# levitator_v1_2023_05_06_11_59_24_UTC.net
KiCad netlist of a schematic drawn in EAGLE
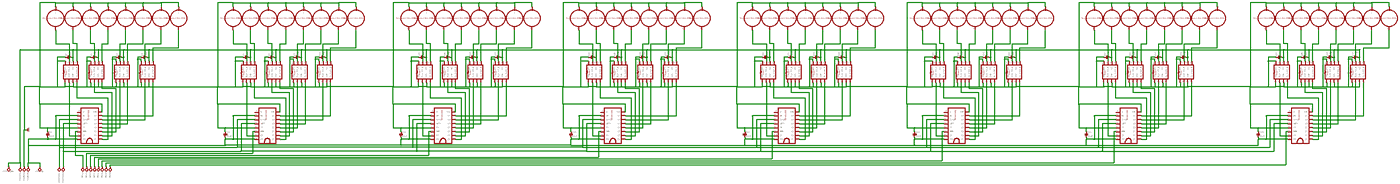
[diagram p0: schematic, sheet 1, overview]
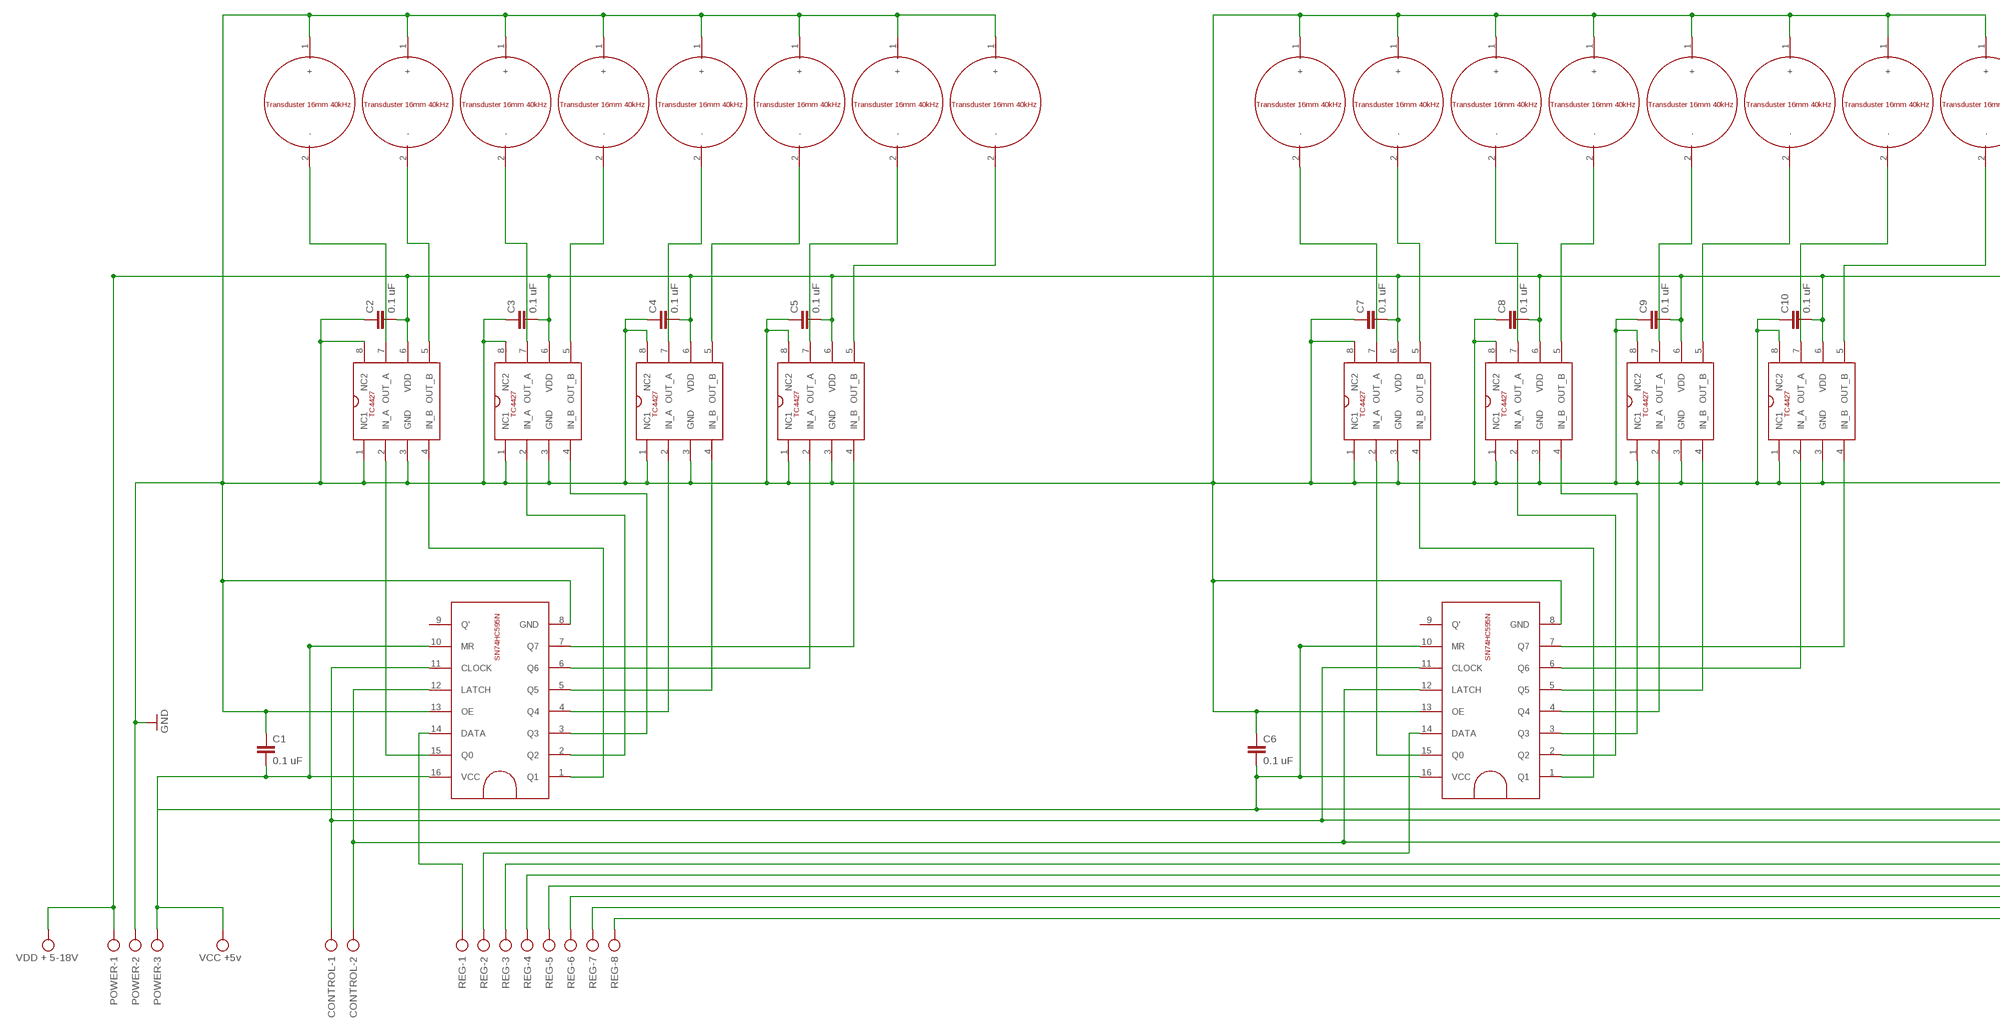
[diagram p1: schematic, sheet 1, part 1 of 4]
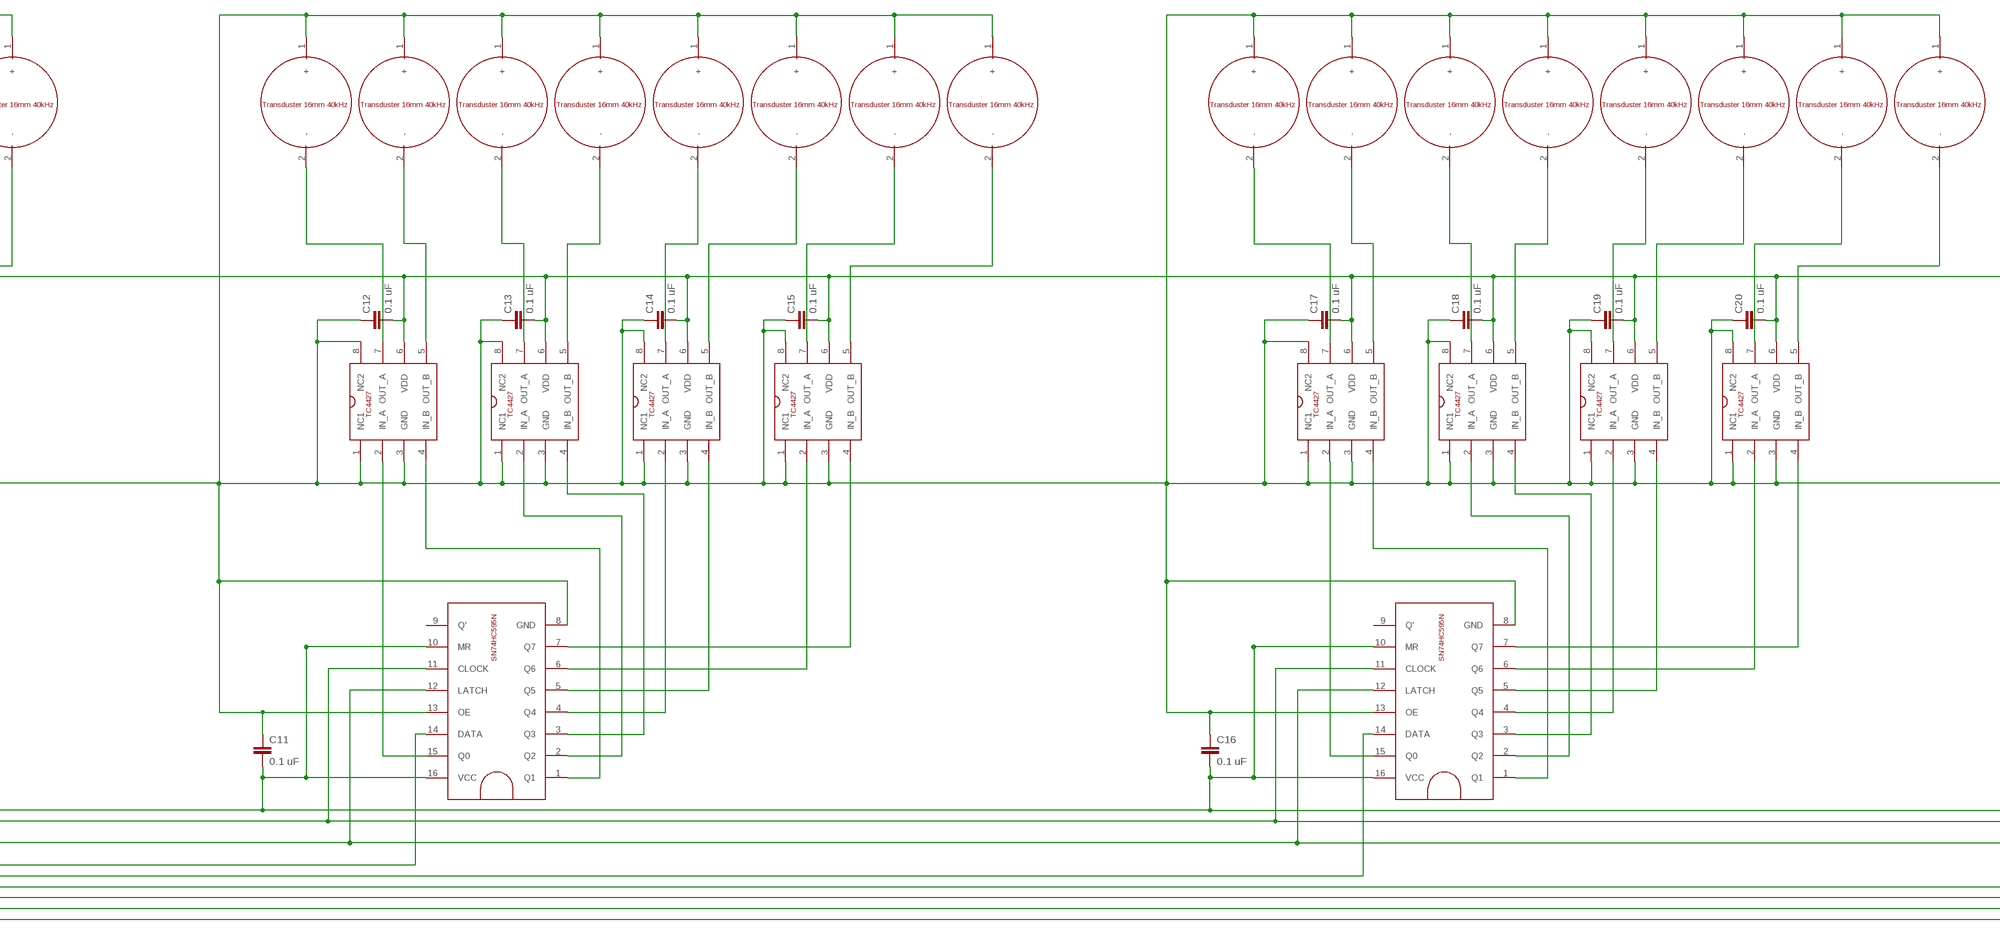
[diagram p2: schematic, sheet 1, part 2 of 4]
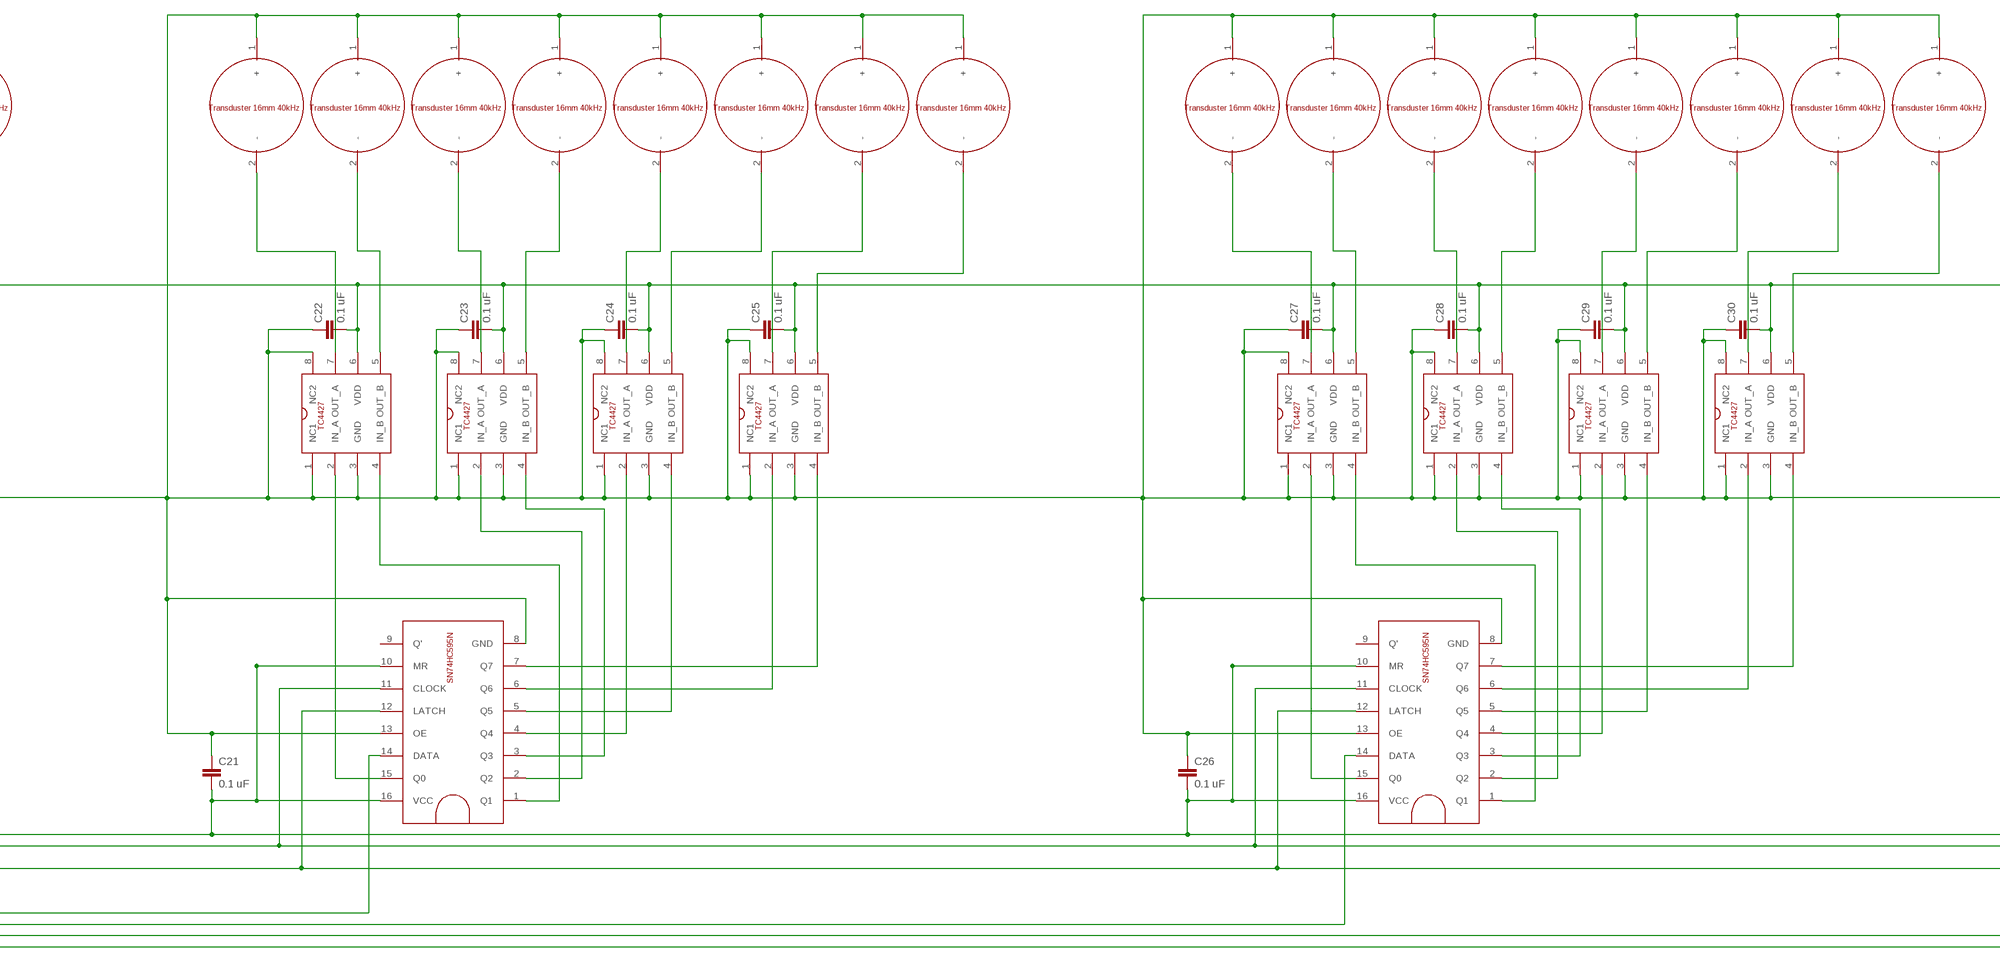
[diagram p3: schematic, sheet 1, part 3 of 4]
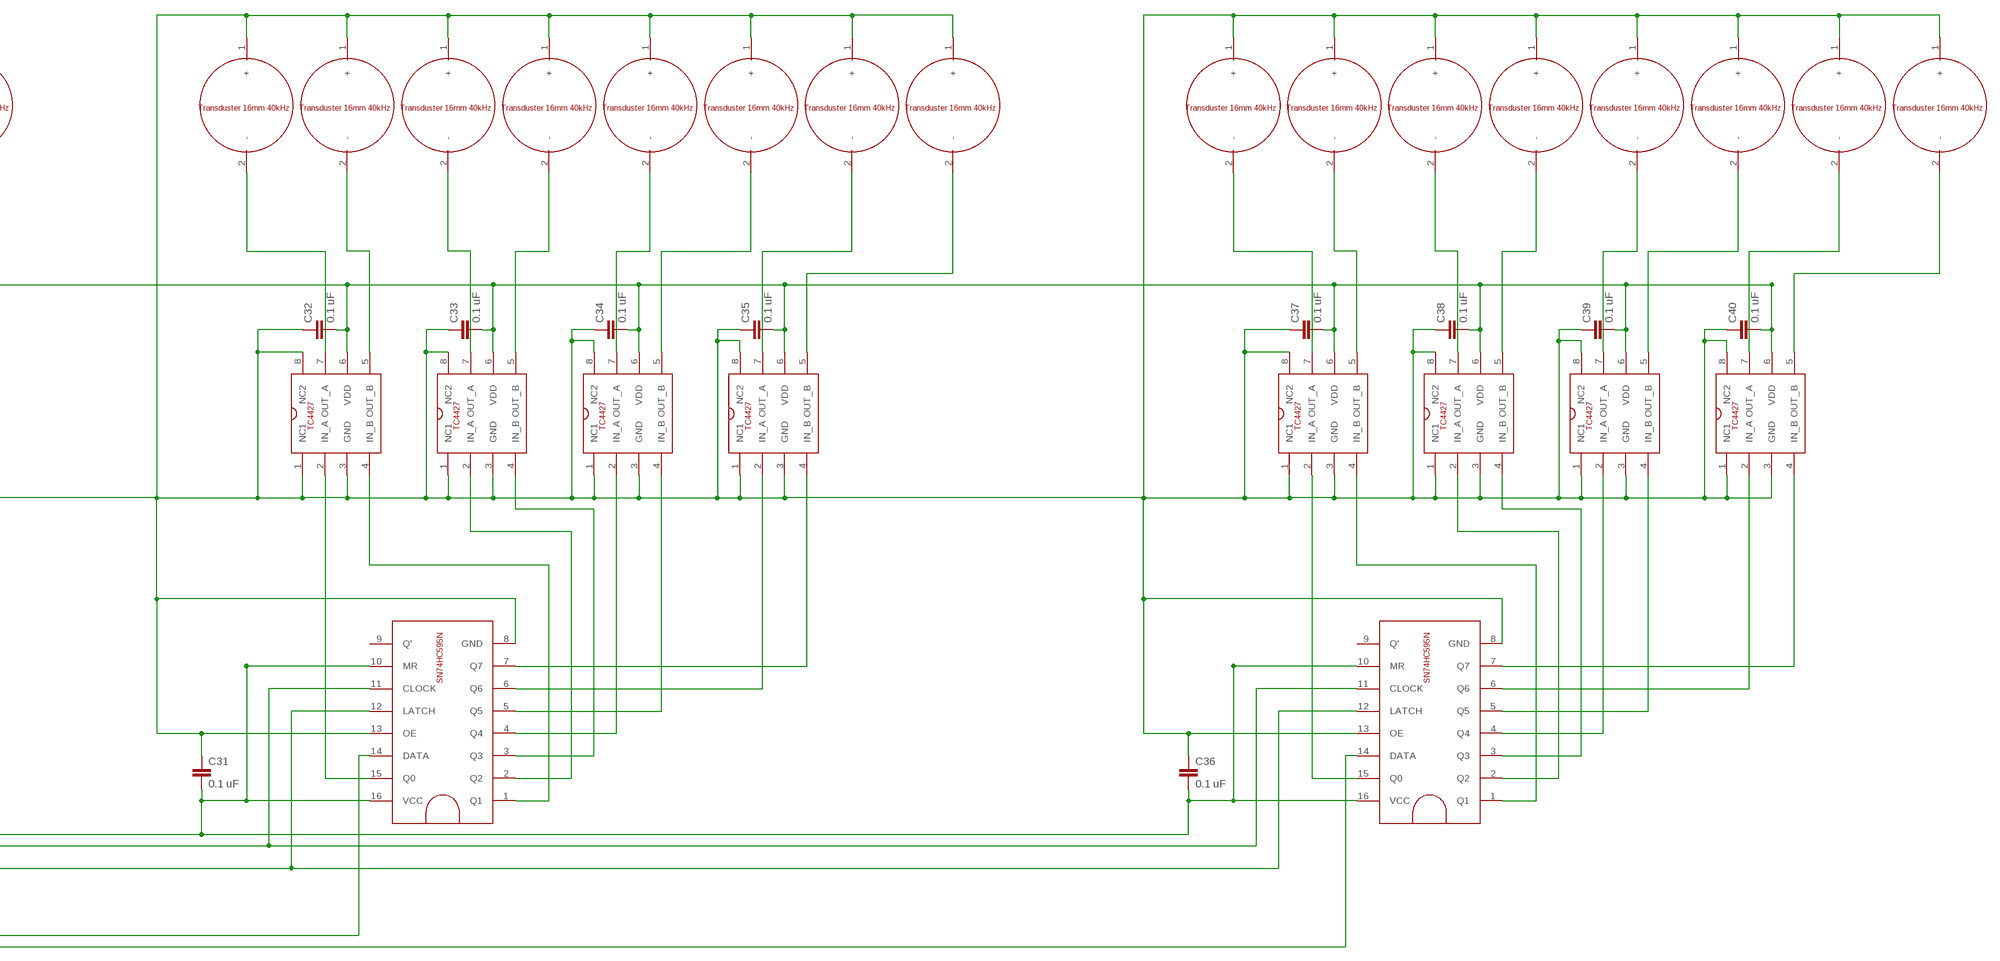
[diagram p4: schematic, sheet 1, part 4 of 4]

(export (version "E")
  (design (tool "Eeschema 10.0.6"))
  (components
    (comp (ref "C1")
      (value "0.1 uF")
      (footprint "eagle-import:C025-025X050")
      (libsource (lib "eagle-import") (part "C-EU025-025X050"))
    )
    (comp (ref "C2")
      (value "0.1 uF")
      (footprint "eagle-import:C025-025X050")
      (libsource (lib "eagle-import") (part "C-EU025-025X050"))
    )
    (comp (ref "C3")
      (value "0.1 uF")
      (footprint "eagle-import:C025-025X050")
      (libsource (lib "eagle-import") (part "C-EU025-025X050"))
    )
    (comp (ref "C4")
      (value "0.1 uF")
      (footprint "eagle-import:C025-025X050")
      (libsource (lib "eagle-import") (part "C-EU025-025X050"))
    )
    (comp (ref "C5")
      (value "0.1 uF")
      (footprint "eagle-import:C025-025X050")
      (libsource (lib "eagle-import") (part "C-EU025-025X050"))
    )
    (comp (ref "C6")
      (value "0.1 uF")
      (footprint "eagle-import:C025-025X050")
      (libsource (lib "eagle-import") (part "C-EU025-025X050"))
    )
    (comp (ref "C7")
      (value "0.1 uF")
      (footprint "eagle-import:C025-025X050")
      (libsource (lib "eagle-import") (part "C-EU025-025X050"))
    )
    (comp (ref "C8")
      (value "0.1 uF")
      (footprint "eagle-import:C025-025X050")
      (libsource (lib "eagle-import") (part "C-EU025-025X050"))
    )
    (comp (ref "C9")
      (value "0.1 uF")
      (footprint "eagle-import:C025-025X050")
      (libsource (lib "eagle-import") (part "C-EU025-025X050"))
    )
    (comp (ref "C10")
      (value "0.1 uF")
      (footprint "eagle-import:C025-025X050")
      (libsource (lib "eagle-import") (part "C-EU025-025X050"))
    )
    (comp (ref "C11")
      (value "0.1 uF")
      (footprint "eagle-import:C025-025X050")
      (libsource (lib "eagle-import") (part "C-EU025-025X050"))
    )
    (comp (ref "C12")
      (value "0.1 uF")
      (footprint "eagle-import:C025-025X050")
      (libsource (lib "eagle-import") (part "C-EU025-025X050"))
    )
    (comp (ref "C13")
      (value "0.1 uF")
      (footprint "eagle-import:C025-025X050")
      (libsource (lib "eagle-import") (part "C-EU025-025X050"))
    )
    (comp (ref "C14")
      (value "0.1 uF")
      (footprint "eagle-import:C025-025X050")
      (libsource (lib "eagle-import") (part "C-EU025-025X050"))
    )
    (comp (ref "C15")
      (value "0.1 uF")
      (footprint "eagle-import:C025-025X050")
      (libsource (lib "eagle-import") (part "C-EU025-025X050"))
    )
    (comp (ref "C16")
      (value "0.1 uF")
      (footprint "eagle-import:C025-025X050")
      (libsource (lib "eagle-import") (part "C-EU025-025X050"))
    )
    (comp (ref "C17")
      (value "0.1 uF")
      (footprint "eagle-import:C025-025X050")
      (libsource (lib "eagle-import") (part "C-EU025-025X050"))
    )
    (comp (ref "C18")
      (value "0.1 uF")
      (footprint "eagle-import:C025-025X050")
      (libsource (lib "eagle-import") (part "C-EU025-025X050"))
    )
    (comp (ref "C19")
      (value "0.1 uF")
      (footprint "eagle-import:C025-025X050")
      (libsource (lib "eagle-import") (part "C-EU025-025X050"))
    )
    (comp (ref "C20")
      (value "0.1 uF")
      (footprint "eagle-import:C025-025X050")
      (libsource (lib "eagle-import") (part "C-EU025-025X050"))
    )
    (comp (ref "C21")
      (value "0.1 uF")
      (footprint "eagle-import:C025-025X050")
      (libsource (lib "eagle-import") (part "C-EU025-025X050"))
    )
    (comp (ref "C22")
      (value "0.1 uF")
      (footprint "eagle-import:C025-025X050")
      (libsource (lib "eagle-import") (part "C-EU025-025X050"))
    )
    (comp (ref "C23")
      (value "0.1 uF")
      (footprint "eagle-import:C025-025X050")
      (libsource (lib "eagle-import") (part "C-EU025-025X050"))
    )
    (comp (ref "C24")
      (value "0.1 uF")
      (footprint "eagle-import:C025-025X050")
      (libsource (lib "eagle-import") (part "C-EU025-025X050"))
    )
    (comp (ref "C25")
      (value "0.1 uF")
      (footprint "eagle-import:C025-025X050")
      (libsource (lib "eagle-import") (part "C-EU025-025X050"))
    )
    (comp (ref "C26")
      (value "0.1 uF")
      (footprint "eagle-import:C025-025X050")
      (libsource (lib "eagle-import") (part "C-EU025-025X050"))
    )
    (comp (ref "C27")
      (value "0.1 uF")
      (footprint "eagle-import:C025-025X050")
      (libsource (lib "eagle-import") (part "C-EU025-025X050"))
    )
    (comp (ref "C28")
      (value "0.1 uF")
      (footprint "eagle-import:C025-025X050")
      (libsource (lib "eagle-import") (part "C-EU025-025X050"))
    )
    (comp (ref "C29")
      (value "0.1 uF")
      (footprint "eagle-import:C025-025X050")
      (libsource (lib "eagle-import") (part "C-EU025-025X050"))
    )
    (comp (ref "C30")
      (value "0.1 uF")
      (footprint "eagle-import:C025-025X050")
      (libsource (lib "eagle-import") (part "C-EU025-025X050"))
    )
    (comp (ref "C31")
      (value "0.1 uF")
      (footprint "eagle-import:C025-025X050")
      (libsource (lib "eagle-import") (part "C-EU025-025X050"))
    )
    (comp (ref "C32")
      (value "0.1 uF")
      (footprint "eagle-import:C025-025X050")
      (libsource (lib "eagle-import") (part "C-EU025-025X050"))
    )
    (comp (ref "C33")
      (value "0.1 uF")
      (footprint "eagle-import:C025-025X050")
      (libsource (lib "eagle-import") (part "C-EU025-025X050"))
    )
    (comp (ref "C34")
      (value "0.1 uF")
      (footprint "eagle-import:C025-025X050")
      (libsource (lib "eagle-import") (part "C-EU025-025X050"))
    )
    (comp (ref "C35")
      (value "0.1 uF")
      (footprint "eagle-import:C025-025X050")
      (libsource (lib "eagle-import") (part "C-EU025-025X050"))
    )
    (comp (ref "C36")
      (value "0.1 uF")
      (footprint "eagle-import:C025-025X050")
      (libsource (lib "eagle-import") (part "C-EU025-025X050"))
    )
    (comp (ref "C37")
      (value "0.1 uF")
      (footprint "eagle-import:C025-025X050")
      (libsource (lib "eagle-import") (part "C-EU025-025X050"))
    )
    (comp (ref "C38")
      (value "0.1 uF")
      (footprint "eagle-import:C025-025X050")
      (libsource (lib "eagle-import") (part "C-EU025-025X050"))
    )
    (comp (ref "C39")
      (value "0.1 uF")
      (footprint "eagle-import:C025-025X050")
      (libsource (lib "eagle-import") (part "C-EU025-025X050"))
    )
    (comp (ref "C40")
      (value "0.1 uF")
      (footprint "eagle-import:C025-025X050")
      (libsource (lib "eagle-import") (part "C-EU025-025X050"))
    )
    (comp (ref "CONTROL")
      (value "AK500/2-H")
      (footprint "eagle-import:AK500_2-H")
      (libsource (lib "eagle-import") (part "AK500/2-H"))
    )
    (comp (ref "POWER")
      (value "AK500/3-H")
      (footprint "eagle-import:AK500_3-H")
      (libsource (lib "eagle-import") (part "AK500/3-H"))
    )
    (comp (ref "REG")
      (value "AK500/8-H")
      (footprint "eagle-import:AK500_8-H")
      (libsource (lib "eagle-import") (part "AK500/8-H"))
    )
    (comp (ref "U$1")
      (value "TC4427")
      (footprint "eagle-import:TC4427")
      (libsource (lib "eagle-import") (part "TC4427"))
    )
    (comp (ref "U$2")
      (value "SN74HC595N")
      (footprint "eagle-import:SN74HC595N")
      (libsource (lib "eagle-import") (part "SN74HC595N"))
    )
    (comp (ref "U$3")
      (value "TC4427")
      (footprint "eagle-import:TC4427")
      (libsource (lib "eagle-import") (part "TC4427"))
    )
    (comp (ref "U$4")
      (value "TC4427")
      (footprint "eagle-import:TC4427")
      (libsource (lib "eagle-import") (part "TC4427"))
    )
    (comp (ref "U$5")
      (value "TC4427")
      (footprint "eagle-import:TC4427")
      (libsource (lib "eagle-import") (part "TC4427"))
    )
    (comp (ref "U$6")
      (value "TRANSDUSTER_16MM_40KHZ")
      (footprint "eagle-import:TRANSDUSTER_16MM_40KHZ")
      (libsource (lib "eagle-import") (part "TRANSDUSTER_16MM_40KHZ"))
    )
    (comp (ref "U$7")
      (value "TRANSDUSTER_16MM_40KHZ")
      (footprint "eagle-import:TRANSDUSTER_16MM_40KHZ")
      (libsource (lib "eagle-import") (part "TRANSDUSTER_16MM_40KHZ"))
    )
    (comp (ref "U$8")
      (value "TRANSDUSTER_16MM_40KHZ")
      (footprint "eagle-import:TRANSDUSTER_16MM_40KHZ")
      (libsource (lib "eagle-import") (part "TRANSDUSTER_16MM_40KHZ"))
    )
    (comp (ref "U$9")
      (value "TRANSDUSTER_16MM_40KHZ")
      (footprint "eagle-import:TRANSDUSTER_16MM_40KHZ")
      (libsource (lib "eagle-import") (part "TRANSDUSTER_16MM_40KHZ"))
    )
    (comp (ref "U$10")
      (value "TRANSDUSTER_16MM_40KHZ")
      (footprint "eagle-import:TRANSDUSTER_16MM_40KHZ")
      (libsource (lib "eagle-import") (part "TRANSDUSTER_16MM_40KHZ"))
    )
    (comp (ref "U$11")
      (value "TRANSDUSTER_16MM_40KHZ")
      (footprint "eagle-import:TRANSDUSTER_16MM_40KHZ")
      (libsource (lib "eagle-import") (part "TRANSDUSTER_16MM_40KHZ"))
    )
    (comp (ref "U$12")
      (value "TRANSDUSTER_16MM_40KHZ")
      (footprint "eagle-import:TRANSDUSTER_16MM_40KHZ")
      (libsource (lib "eagle-import") (part "TRANSDUSTER_16MM_40KHZ"))
    )
    (comp (ref "U$13")
      (value "TRANSDUSTER_16MM_40KHZ")
      (footprint "eagle-import:TRANSDUSTER_16MM_40KHZ")
      (libsource (lib "eagle-import") (part "TRANSDUSTER_16MM_40KHZ"))
    )
    (comp (ref "U$14")
      (value "TC4427")
      (footprint "eagle-import:TC4427")
      (libsource (lib "eagle-import") (part "TC4427"))
    )
    (comp (ref "U$15")
      (value "SN74HC595N")
      (footprint "eagle-import:SN74HC595N")
      (libsource (lib "eagle-import") (part "SN74HC595N"))
    )
    (comp (ref "U$16")
      (value "TC4427")
      (footprint "eagle-import:TC4427")
      (libsource (lib "eagle-import") (part "TC4427"))
    )
    (comp (ref "U$17")
      (value "TC4427")
      (footprint "eagle-import:TC4427")
      (libsource (lib "eagle-import") (part "TC4427"))
    )
    (comp (ref "U$18")
      (value "TC4427")
      (footprint "eagle-import:TC4427")
      (libsource (lib "eagle-import") (part "TC4427"))
    )
    (comp (ref "U$19")
      (value "TRANSDUSTER_16MM_40KHZ")
      (footprint "eagle-import:TRANSDUSTER_16MM_40KHZ")
      (libsource (lib "eagle-import") (part "TRANSDUSTER_16MM_40KHZ"))
    )
    (comp (ref "U$20")
      (value "TRANSDUSTER_16MM_40KHZ")
      (footprint "eagle-import:TRANSDUSTER_16MM_40KHZ")
      (libsource (lib "eagle-import") (part "TRANSDUSTER_16MM_40KHZ"))
    )
    (comp (ref "U$21")
      (value "TRANSDUSTER_16MM_40KHZ")
      (footprint "eagle-import:TRANSDUSTER_16MM_40KHZ")
      (libsource (lib "eagle-import") (part "TRANSDUSTER_16MM_40KHZ"))
    )
    (comp (ref "U$22")
      (value "TRANSDUSTER_16MM_40KHZ")
      (footprint "eagle-import:TRANSDUSTER_16MM_40KHZ")
      (libsource (lib "eagle-import") (part "TRANSDUSTER_16MM_40KHZ"))
    )
    (comp (ref "U$23")
      (value "TRANSDUSTER_16MM_40KHZ")
      (footprint "eagle-import:TRANSDUSTER_16MM_40KHZ")
      (libsource (lib "eagle-import") (part "TRANSDUSTER_16MM_40KHZ"))
    )
    (comp (ref "U$24")
      (value "TRANSDUSTER_16MM_40KHZ")
      (footprint "eagle-import:TRANSDUSTER_16MM_40KHZ")
      (libsource (lib "eagle-import") (part "TRANSDUSTER_16MM_40KHZ"))
    )
    (comp (ref "U$25")
      (value "TRANSDUSTER_16MM_40KHZ")
      (footprint "eagle-import:TRANSDUSTER_16MM_40KHZ")
      (libsource (lib "eagle-import") (part "TRANSDUSTER_16MM_40KHZ"))
    )
    (comp (ref "U$26")
      (value "TRANSDUSTER_16MM_40KHZ")
      (footprint "eagle-import:TRANSDUSTER_16MM_40KHZ")
      (libsource (lib "eagle-import") (part "TRANSDUSTER_16MM_40KHZ"))
    )
    (comp (ref "U$27")
      (value "TC4427")
      (footprint "eagle-import:TC4427")
      (libsource (lib "eagle-import") (part "TC4427"))
    )
    (comp (ref "U$28")
      (value "SN74HC595N")
      (footprint "eagle-import:SN74HC595N")
      (libsource (lib "eagle-import") (part "SN74HC595N"))
    )
    (comp (ref "U$29")
      (value "TC4427")
      (footprint "eagle-import:TC4427")
      (libsource (lib "eagle-import") (part "TC4427"))
    )
    (comp (ref "U$30")
      (value "TC4427")
      (footprint "eagle-import:TC4427")
      (libsource (lib "eagle-import") (part "TC4427"))
    )
    (comp (ref "U$31")
      (value "TC4427")
      (footprint "eagle-import:TC4427")
      (libsource (lib "eagle-import") (part "TC4427"))
    )
    (comp (ref "U$32")
      (value "TRANSDUSTER_16MM_40KHZ")
      (footprint "eagle-import:TRANSDUSTER_16MM_40KHZ")
      (libsource (lib "eagle-import") (part "TRANSDUSTER_16MM_40KHZ"))
    )
    (comp (ref "U$33")
      (value "TRANSDUSTER_16MM_40KHZ")
      (footprint "eagle-import:TRANSDUSTER_16MM_40KHZ")
      (libsource (lib "eagle-import") (part "TRANSDUSTER_16MM_40KHZ"))
    )
    (comp (ref "U$34")
      (value "TRANSDUSTER_16MM_40KHZ")
      (footprint "eagle-import:TRANSDUSTER_16MM_40KHZ")
      (libsource (lib "eagle-import") (part "TRANSDUSTER_16MM_40KHZ"))
    )
    (comp (ref "U$35")
      (value "TRANSDUSTER_16MM_40KHZ")
      (footprint "eagle-import:TRANSDUSTER_16MM_40KHZ")
      (libsource (lib "eagle-import") (part "TRANSDUSTER_16MM_40KHZ"))
    )
    (comp (ref "U$36")
      (value "TRANSDUSTER_16MM_40KHZ")
      (footprint "eagle-import:TRANSDUSTER_16MM_40KHZ")
      (libsource (lib "eagle-import") (part "TRANSDUSTER_16MM_40KHZ"))
    )
    (comp (ref "U$37")
      (value "TRANSDUSTER_16MM_40KHZ")
      (footprint "eagle-import:TRANSDUSTER_16MM_40KHZ")
      (libsource (lib "eagle-import") (part "TRANSDUSTER_16MM_40KHZ"))
    )
    (comp (ref "U$38")
      (value "TRANSDUSTER_16MM_40KHZ")
      (footprint "eagle-import:TRANSDUSTER_16MM_40KHZ")
      (libsource (lib "eagle-import") (part "TRANSDUSTER_16MM_40KHZ"))
    )
    (comp (ref "U$39")
      (value "TRANSDUSTER_16MM_40KHZ")
      (footprint "eagle-import:TRANSDUSTER_16MM_40KHZ")
      (libsource (lib "eagle-import") (part "TRANSDUSTER_16MM_40KHZ"))
    )
    (comp (ref "U$40")
      (value "TC4427")
      (footprint "eagle-import:TC4427")
      (libsource (lib "eagle-import") (part "TC4427"))
    )
    (comp (ref "U$41")
      (value "SN74HC595N")
      (footprint "eagle-import:SN74HC595N")
      (libsource (lib "eagle-import") (part "SN74HC595N"))
    )
    (comp (ref "U$42")
      (value "TC4427")
      (footprint "eagle-import:TC4427")
      (libsource (lib "eagle-import") (part "TC4427"))
    )
    (comp (ref "U$43")
      (value "TC4427")
      (footprint "eagle-import:TC4427")
      (libsource (lib "eagle-import") (part "TC4427"))
    )
    (comp (ref "U$44")
      (value "TC4427")
      (footprint "eagle-import:TC4427")
      (libsource (lib "eagle-import") (part "TC4427"))
    )
    (comp (ref "U$45")
      (value "TRANSDUSTER_16MM_40KHZ")
      (footprint "eagle-import:TRANSDUSTER_16MM_40KHZ")
      (libsource (lib "eagle-import") (part "TRANSDUSTER_16MM_40KHZ"))
    )
    (comp (ref "U$46")
      (value "TRANSDUSTER_16MM_40KHZ")
      (footprint "eagle-import:TRANSDUSTER_16MM_40KHZ")
      (libsource (lib "eagle-import") (part "TRANSDUSTER_16MM_40KHZ"))
    )
    (comp (ref "U$47")
      (value "TRANSDUSTER_16MM_40KHZ")
      (footprint "eagle-import:TRANSDUSTER_16MM_40KHZ")
      (libsource (lib "eagle-import") (part "TRANSDUSTER_16MM_40KHZ"))
    )
    (comp (ref "U$48")
      (value "TRANSDUSTER_16MM_40KHZ")
      (footprint "eagle-import:TRANSDUSTER_16MM_40KHZ")
      (libsource (lib "eagle-import") (part "TRANSDUSTER_16MM_40KHZ"))
    )
    (comp (ref "U$49")
      (value "TRANSDUSTER_16MM_40KHZ")
      (footprint "eagle-import:TRANSDUSTER_16MM_40KHZ")
      (libsource (lib "eagle-import") (part "TRANSDUSTER_16MM_40KHZ"))
    )
    (comp (ref "U$50")
      (value "TRANSDUSTER_16MM_40KHZ")
      (footprint "eagle-import:TRANSDUSTER_16MM_40KHZ")
      (libsource (lib "eagle-import") (part "TRANSDUSTER_16MM_40KHZ"))
    )
    (comp (ref "U$51")
      (value "TRANSDUSTER_16MM_40KHZ")
      (footprint "eagle-import:TRANSDUSTER_16MM_40KHZ")
      (libsource (lib "eagle-import") (part "TRANSDUSTER_16MM_40KHZ"))
    )
    (comp (ref "U$52")
      (value "TRANSDUSTER_16MM_40KHZ")
      (footprint "eagle-import:TRANSDUSTER_16MM_40KHZ")
      (libsource (lib "eagle-import") (part "TRANSDUSTER_16MM_40KHZ"))
    )
    (comp (ref "U$53")
      (value "TC4427")
      (footprint "eagle-import:TC4427")
      (libsource (lib "eagle-import") (part "TC4427"))
    )
    (comp (ref "U$54")
      (value "SN74HC595N")
      (footprint "eagle-import:SN74HC595N")
      (libsource (lib "eagle-import") (part "SN74HC595N"))
    )
    (comp (ref "U$55")
      (value "TC4427")
      (footprint "eagle-import:TC4427")
      (libsource (lib "eagle-import") (part "TC4427"))
    )
    (comp (ref "U$56")
      (value "TC4427")
      (footprint "eagle-import:TC4427")
      (libsource (lib "eagle-import") (part "TC4427"))
    )
    (comp (ref "U$57")
      (value "TC4427")
      (footprint "eagle-import:TC4427")
      (libsource (lib "eagle-import") (part "TC4427"))
    )
    (comp (ref "U$58")
      (value "TRANSDUSTER_16MM_40KHZ")
      (footprint "eagle-import:TRANSDUSTER_16MM_40KHZ")
      (libsource (lib "eagle-import") (part "TRANSDUSTER_16MM_40KHZ"))
    )
    (comp (ref "U$59")
      (value "TRANSDUSTER_16MM_40KHZ")
      (footprint "eagle-import:TRANSDUSTER_16MM_40KHZ")
      (libsource (lib "eagle-import") (part "TRANSDUSTER_16MM_40KHZ"))
    )
    (comp (ref "U$60")
      (value "TRANSDUSTER_16MM_40KHZ")
      (footprint "eagle-import:TRANSDUSTER_16MM_40KHZ")
      (libsource (lib "eagle-import") (part "TRANSDUSTER_16MM_40KHZ"))
    )
    (comp (ref "U$61")
      (value "TRANSDUSTER_16MM_40KHZ")
      (footprint "eagle-import:TRANSDUSTER_16MM_40KHZ")
      (libsource (lib "eagle-import") (part "TRANSDUSTER_16MM_40KHZ"))
    )
    (comp (ref "U$62")
      (value "TRANSDUSTER_16MM_40KHZ")
      (footprint "eagle-import:TRANSDUSTER_16MM_40KHZ")
      (libsource (lib "eagle-import") (part "TRANSDUSTER_16MM_40KHZ"))
    )
    (comp (ref "U$63")
      (value "TRANSDUSTER_16MM_40KHZ")
      (footprint "eagle-import:TRANSDUSTER_16MM_40KHZ")
      (libsource (lib "eagle-import") (part "TRANSDUSTER_16MM_40KHZ"))
    )
    (comp (ref "U$64")
      (value "TRANSDUSTER_16MM_40KHZ")
      (footprint "eagle-import:TRANSDUSTER_16MM_40KHZ")
      (libsource (lib "eagle-import") (part "TRANSDUSTER_16MM_40KHZ"))
    )
    (comp (ref "U$65")
      (value "TRANSDUSTER_16MM_40KHZ")
      (footprint "eagle-import:TRANSDUSTER_16MM_40KHZ")
      (libsource (lib "eagle-import") (part "TRANSDUSTER_16MM_40KHZ"))
    )
    (comp (ref "U$66")
      (value "TC4427")
      (footprint "eagle-import:TC4427")
      (libsource (lib "eagle-import") (part "TC4427"))
    )
    (comp (ref "U$67")
      (value "SN74HC595N")
      (footprint "eagle-import:SN74HC595N")
      (libsource (lib "eagle-import") (part "SN74HC595N"))
    )
    (comp (ref "U$68")
      (value "TC4427")
      (footprint "eagle-import:TC4427")
      (libsource (lib "eagle-import") (part "TC4427"))
    )
    (comp (ref "U$69")
      (value "TC4427")
      (footprint "eagle-import:TC4427")
      (libsource (lib "eagle-import") (part "TC4427"))
    )
    (comp (ref "U$70")
      (value "TC4427")
      (footprint "eagle-import:TC4427")
      (libsource (lib "eagle-import") (part "TC4427"))
    )
    (comp (ref "U$71")
      (value "TRANSDUSTER_16MM_40KHZ")
      (footprint "eagle-import:TRANSDUSTER_16MM_40KHZ")
      (libsource (lib "eagle-import") (part "TRANSDUSTER_16MM_40KHZ"))
    )
    (comp (ref "U$72")
      (value "TRANSDUSTER_16MM_40KHZ")
      (footprint "eagle-import:TRANSDUSTER_16MM_40KHZ")
      (libsource (lib "eagle-import") (part "TRANSDUSTER_16MM_40KHZ"))
    )
    (comp (ref "U$73")
      (value "TRANSDUSTER_16MM_40KHZ")
      (footprint "eagle-import:TRANSDUSTER_16MM_40KHZ")
      (libsource (lib "eagle-import") (part "TRANSDUSTER_16MM_40KHZ"))
    )
    (comp (ref "U$74")
      (value "TRANSDUSTER_16MM_40KHZ")
      (footprint "eagle-import:TRANSDUSTER_16MM_40KHZ")
      (libsource (lib "eagle-import") (part "TRANSDUSTER_16MM_40KHZ"))
    )
    (comp (ref "U$75")
      (value "TRANSDUSTER_16MM_40KHZ")
      (footprint "eagle-import:TRANSDUSTER_16MM_40KHZ")
      (libsource (lib "eagle-import") (part "TRANSDUSTER_16MM_40KHZ"))
    )
    (comp (ref "U$76")
      (value "TRANSDUSTER_16MM_40KHZ")
      (footprint "eagle-import:TRANSDUSTER_16MM_40KHZ")
      (libsource (lib "eagle-import") (part "TRANSDUSTER_16MM_40KHZ"))
    )
    (comp (ref "U$77")
      (value "TRANSDUSTER_16MM_40KHZ")
      (footprint "eagle-import:TRANSDUSTER_16MM_40KHZ")
      (libsource (lib "eagle-import") (part "TRANSDUSTER_16MM_40KHZ"))
    )
    (comp (ref "U$78")
      (value "TRANSDUSTER_16MM_40KHZ")
      (footprint "eagle-import:TRANSDUSTER_16MM_40KHZ")
      (libsource (lib "eagle-import") (part "TRANSDUSTER_16MM_40KHZ"))
    )
    (comp (ref "U$79")
      (value "TC4427")
      (footprint "eagle-import:TC4427")
      (libsource (lib "eagle-import") (part "TC4427"))
    )
    (comp (ref "U$80")
      (value "SN74HC595N")
      (footprint "eagle-import:SN74HC595N")
      (libsource (lib "eagle-import") (part "SN74HC595N"))
    )
    (comp (ref "U$81")
      (value "TC4427")
      (footprint "eagle-import:TC4427")
      (libsource (lib "eagle-import") (part "TC4427"))
    )
    (comp (ref "U$82")
      (value "TC4427")
      (footprint "eagle-import:TC4427")
      (libsource (lib "eagle-import") (part "TC4427"))
    )
    (comp (ref "U$83")
      (value "TC4427")
      (footprint "eagle-import:TC4427")
      (libsource (lib "eagle-import") (part "TC4427"))
    )
    (comp (ref "U$84")
      (value "TRANSDUSTER_16MM_40KHZ")
      (footprint "eagle-import:TRANSDUSTER_16MM_40KHZ")
      (libsource (lib "eagle-import") (part "TRANSDUSTER_16MM_40KHZ"))
    )
    (comp (ref "U$85")
      (value "TRANSDUSTER_16MM_40KHZ")
      (footprint "eagle-import:TRANSDUSTER_16MM_40KHZ")
      (libsource (lib "eagle-import") (part "TRANSDUSTER_16MM_40KHZ"))
    )
    (comp (ref "U$86")
      (value "TRANSDUSTER_16MM_40KHZ")
      (footprint "eagle-import:TRANSDUSTER_16MM_40KHZ")
      (libsource (lib "eagle-import") (part "TRANSDUSTER_16MM_40KHZ"))
    )
    (comp (ref "U$87")
      (value "TRANSDUSTER_16MM_40KHZ")
      (footprint "eagle-import:TRANSDUSTER_16MM_40KHZ")
      (libsource (lib "eagle-import") (part "TRANSDUSTER_16MM_40KHZ"))
    )
    (comp (ref "U$88")
      (value "TRANSDUSTER_16MM_40KHZ")
      (footprint "eagle-import:TRANSDUSTER_16MM_40KHZ")
      (libsource (lib "eagle-import") (part "TRANSDUSTER_16MM_40KHZ"))
    )
    (comp (ref "U$89")
      (value "TRANSDUSTER_16MM_40KHZ")
      (footprint "eagle-import:TRANSDUSTER_16MM_40KHZ")
      (libsource (lib "eagle-import") (part "TRANSDUSTER_16MM_40KHZ"))
    )
    (comp (ref "U$90")
      (value "TRANSDUSTER_16MM_40KHZ")
      (footprint "eagle-import:TRANSDUSTER_16MM_40KHZ")
      (libsource (lib "eagle-import") (part "TRANSDUSTER_16MM_40KHZ"))
    )
    (comp (ref "U$91")
      (value "TRANSDUSTER_16MM_40KHZ")
      (footprint "eagle-import:TRANSDUSTER_16MM_40KHZ")
      (libsource (lib "eagle-import") (part "TRANSDUSTER_16MM_40KHZ"))
    )
    (comp (ref "U$92")
      (value "TC4427")
      (footprint "eagle-import:TC4427")
      (libsource (lib "eagle-import") (part "TC4427"))
    )
    (comp (ref "U$93")
      (value "SN74HC595N")
      (footprint "eagle-import:SN74HC595N")
      (libsource (lib "eagle-import") (part "SN74HC595N"))
    )
    (comp (ref "U$94")
      (value "TC4427")
      (footprint "eagle-import:TC4427")
      (libsource (lib "eagle-import") (part "TC4427"))
    )
    (comp (ref "U$95")
      (value "TC4427")
      (footprint "eagle-import:TC4427")
      (libsource (lib "eagle-import") (part "TC4427"))
    )
    (comp (ref "U$96")
      (value "TC4427")
      (footprint "eagle-import:TC4427")
      (libsource (lib "eagle-import") (part "TC4427"))
    )
    (comp (ref "U$97")
      (value "TRANSDUSTER_16MM_40KHZ")
      (footprint "eagle-import:TRANSDUSTER_16MM_40KHZ")
      (libsource (lib "eagle-import") (part "TRANSDUSTER_16MM_40KHZ"))
    )
    (comp (ref "U$98")
      (value "TRANSDUSTER_16MM_40KHZ")
      (footprint "eagle-import:TRANSDUSTER_16MM_40KHZ")
      (libsource (lib "eagle-import") (part "TRANSDUSTER_16MM_40KHZ"))
    )
    (comp (ref "U$99")
      (value "TRANSDUSTER_16MM_40KHZ")
      (footprint "eagle-import:TRANSDUSTER_16MM_40KHZ")
      (libsource (lib "eagle-import") (part "TRANSDUSTER_16MM_40KHZ"))
    )
    (comp (ref "U$100")
      (value "TRANSDUSTER_16MM_40KHZ")
      (footprint "eagle-import:TRANSDUSTER_16MM_40KHZ")
      (libsource (lib "eagle-import") (part "TRANSDUSTER_16MM_40KHZ"))
    )
    (comp (ref "U$101")
      (value "TRANSDUSTER_16MM_40KHZ")
      (footprint "eagle-import:TRANSDUSTER_16MM_40KHZ")
      (libsource (lib "eagle-import") (part "TRANSDUSTER_16MM_40KHZ"))
    )
    (comp (ref "U$102")
      (value "TRANSDUSTER_16MM_40KHZ")
      (footprint "eagle-import:TRANSDUSTER_16MM_40KHZ")
      (libsource (lib "eagle-import") (part "TRANSDUSTER_16MM_40KHZ"))
    )
    (comp (ref "U$103")
      (value "TRANSDUSTER_16MM_40KHZ")
      (footprint "eagle-import:TRANSDUSTER_16MM_40KHZ")
      (libsource (lib "eagle-import") (part "TRANSDUSTER_16MM_40KHZ"))
    )
    (comp (ref "U$104")
      (value "TRANSDUSTER_16MM_40KHZ")
      (footprint "eagle-import:TRANSDUSTER_16MM_40KHZ")
      (libsource (lib "eagle-import") (part "TRANSDUSTER_16MM_40KHZ"))
    )
  )
  (nets
    (net (code "1") (name "GND") (class "Default")
      (node (ref "C1") (pin "1") (pinfunction "1_1") (pintype "passive"))
      (node (ref "C10") (pin "1") (pinfunction "1_1") (pintype "passive"))
      (node (ref "C11") (pin "1") (pinfunction "1_1") (pintype "passive"))
      (node (ref "C12") (pin "1") (pinfunction "1_1") (pintype "passive"))
      (node (ref "C13") (pin "1") (pinfunction "1_1") (pintype "passive"))
      (node (ref "C14") (pin "1") (pinfunction "1_1") (pintype "passive"))
      (node (ref "C15") (pin "1") (pinfunction "1_1") (pintype "passive"))
      (node (ref "C16") (pin "1") (pinfunction "1_1") (pintype "passive"))
      (node (ref "C17") (pin "1") (pinfunction "1_1") (pintype "passive"))
      (node (ref "C18") (pin "1") (pinfunction "1_1") (pintype "passive"))
      (node (ref "C19") (pin "1") (pinfunction "1_1") (pintype "passive"))
      (node (ref "C2") (pin "1") (pinfunction "1_1") (pintype "passive"))
      (node (ref "C20") (pin "1") (pinfunction "1_1") (pintype "passive"))
      (node (ref "C21") (pin "1") (pinfunction "1_1") (pintype "passive"))
      (node (ref "C22") (pin "1") (pinfunction "1_1") (pintype "passive"))
      (node (ref "C23") (pin "1") (pinfunction "1_1") (pintype "passive"))
      (node (ref "C24") (pin "1") (pinfunction "1_1") (pintype "passive"))
      (node (ref "C25") (pin "1") (pinfunction "1_1") (pintype "passive"))
      (node (ref "C26") (pin "1") (pinfunction "1_1") (pintype "passive"))
      (node (ref "C27") (pin "1") (pinfunction "1_1") (pintype "passive"))
      (node (ref "C28") (pin "1") (pinfunction "1_1") (pintype "passive"))
      (node (ref "C29") (pin "1") (pinfunction "1_1") (pintype "passive"))
      (node (ref "C3") (pin "1") (pinfunction "1_1") (pintype "passive"))
      (node (ref "C30") (pin "1") (pinfunction "1_1") (pintype "passive"))
      (node (ref "C31") (pin "1") (pinfunction "1_1") (pintype "passive"))
      (node (ref "C32") (pin "1") (pinfunction "1_1") (pintype "passive"))
      (node (ref "C33") (pin "1") (pinfunction "1_1") (pintype "passive"))
      (node (ref "C34") (pin "1") (pinfunction "1_1") (pintype "passive"))
      (node (ref "C35") (pin "1") (pinfunction "1_1") (pintype "passive"))
      (node (ref "C36") (pin "1") (pinfunction "1_1") (pintype "passive"))
      (node (ref "C37") (pin "1") (pinfunction "1_1") (pintype "passive"))
      (node (ref "C38") (pin "1") (pinfunction "1_1") (pintype "passive"))
      (node (ref "C39") (pin "1") (pinfunction "1_1") (pintype "passive"))
      (node (ref "C4") (pin "1") (pinfunction "1_1") (pintype "passive"))
      (node (ref "C40") (pin "1") (pinfunction "1_1") (pintype "passive"))
      (node (ref "C5") (pin "1") (pinfunction "1_1") (pintype "passive"))
      (node (ref "C6") (pin "1") (pinfunction "1_1") (pintype "passive"))
      (node (ref "C7") (pin "1") (pinfunction "1_1") (pintype "passive"))
      (node (ref "C8") (pin "1") (pinfunction "1_1") (pintype "passive"))
      (node (ref "C9") (pin "1") (pinfunction "1_1") (pintype "passive"))
      (node (ref "POWER") (pin "2") (pinfunction "KL_2") (pintype "passive"))
      (node (ref "U$1") (pin "1") (pinfunction "NC1_1") (pintype "bidirectional"))
      (node (ref "U$1") (pin "3") (pinfunction "GND_3") (pintype "bidirectional"))
      (node (ref "U$1") (pin "8") (pinfunction "NC2_8") (pintype "bidirectional"))
      (node (ref "U$10") (pin "1") (pinfunction "+_1") (pintype "bidirectional"))
      (node (ref "U$100") (pin "1") (pinfunction "+_1") (pintype "bidirectional"))
      (node (ref "U$101") (pin "1") (pinfunction "+_1") (pintype "bidirectional"))
      (node (ref "U$102") (pin "1") (pinfunction "+_1") (pintype "bidirectional"))
      (node (ref "U$103") (pin "1") (pinfunction "+_1") (pintype "bidirectional"))
      (node (ref "U$104") (pin "1") (pinfunction "+_1") (pintype "bidirectional"))
      (node (ref "U$11") (pin "1") (pinfunction "+_1") (pintype "bidirectional"))
      (node (ref "U$12") (pin "1") (pinfunction "+_1") (pintype "bidirectional"))
      (node (ref "U$13") (pin "1") (pinfunction "+_1") (pintype "bidirectional"))
      (node (ref "U$14") (pin "1") (pinfunction "NC1_1") (pintype "bidirectional"))
      (node (ref "U$14") (pin "3") (pinfunction "GND_3") (pintype "bidirectional"))
      (node (ref "U$14") (pin "8") (pinfunction "NC2_8") (pintype "bidirectional"))
      (node (ref "U$15") (pin "13") (pinfunction "OE_13") (pintype "bidirectional"))
      (node (ref "U$15") (pin "8") (pinfunction "GND_8") (pintype "bidirectional"))
      (node (ref "U$16") (pin "1") (pinfunction "NC1_1") (pintype "bidirectional"))
      (node (ref "U$16") (pin "3") (pinfunction "GND_3") (pintype "bidirectional"))
      (node (ref "U$16") (pin "8") (pinfunction "NC2_8") (pintype "bidirectional"))
      (node (ref "U$17") (pin "1") (pinfunction "NC1_1") (pintype "bidirectional"))
      (node (ref "U$17") (pin "3") (pinfunction "GND_3") (pintype "bidirectional"))
      (node (ref "U$17") (pin "8") (pinfunction "NC2_8") (pintype "bidirectional"))
      (node (ref "U$18") (pin "1") (pinfunction "NC1_1") (pintype "bidirectional"))
      (node (ref "U$18") (pin "3") (pinfunction "GND_3") (pintype "bidirectional"))
      (node (ref "U$18") (pin "8") (pinfunction "NC2_8") (pintype "bidirectional"))
      (node (ref "U$19") (pin "1") (pinfunction "+_1") (pintype "bidirectional"))
      (node (ref "U$2") (pin "13") (pinfunction "OE_13") (pintype "bidirectional"))
      (node (ref "U$2") (pin "8") (pinfunction "GND_8") (pintype "bidirectional"))
      (node (ref "U$20") (pin "1") (pinfunction "+_1") (pintype "bidirectional"))
      (node (ref "U$21") (pin "1") (pinfunction "+_1") (pintype "bidirectional"))
      (node (ref "U$22") (pin "1") (pinfunction "+_1") (pintype "bidirectional"))
      (node (ref "U$23") (pin "1") (pinfunction "+_1") (pintype "bidirectional"))
      (node (ref "U$24") (pin "1") (pinfunction "+_1") (pintype "bidirectional"))
      (node (ref "U$25") (pin "1") (pinfunction "+_1") (pintype "bidirectional"))
      (node (ref "U$26") (pin "1") (pinfunction "+_1") (pintype "bidirectional"))
      (node (ref "U$27") (pin "1") (pinfunction "NC1_1") (pintype "bidirectional"))
      (node (ref "U$27") (pin "3") (pinfunction "GND_3") (pintype "bidirectional"))
      (node (ref "U$27") (pin "8") (pinfunction "NC2_8") (pintype "bidirectional"))
      (node (ref "U$28") (pin "13") (pinfunction "OE_13") (pintype "bidirectional"))
      (node (ref "U$28") (pin "8") (pinfunction "GND_8") (pintype "bidirectional"))
      (node (ref "U$29") (pin "1") (pinfunction "NC1_1") (pintype "bidirectional"))
      (node (ref "U$29") (pin "3") (pinfunction "GND_3") (pintype "bidirectional"))
      (node (ref "U$29") (pin "8") (pinfunction "NC2_8") (pintype "bidirectional"))
      (node (ref "U$3") (pin "1") (pinfunction "NC1_1") (pintype "bidirectional"))
      (node (ref "U$3") (pin "3") (pinfunction "GND_3") (pintype "bidirectional"))
      (node (ref "U$3") (pin "8") (pinfunction "NC2_8") (pintype "bidirectional"))
      (node (ref "U$30") (pin "1") (pinfunction "NC1_1") (pintype "bidirectional"))
      (node (ref "U$30") (pin "3") (pinfunction "GND_3") (pintype "bidirectional"))
      (node (ref "U$30") (pin "8") (pinfunction "NC2_8") (pintype "bidirectional"))
      (node (ref "U$31") (pin "1") (pinfunction "NC1_1") (pintype "bidirectional"))
      (node (ref "U$31") (pin "3") (pinfunction "GND_3") (pintype "bidirectional"))
      (node (ref "U$31") (pin "8") (pinfunction "NC2_8") (pintype "bidirectional"))
      (node (ref "U$32") (pin "1") (pinfunction "+_1") (pintype "bidirectional"))
      (node (ref "U$33") (pin "1") (pinfunction "+_1") (pintype "bidirectional"))
      (node (ref "U$34") (pin "1") (pinfunction "+_1") (pintype "bidirectional"))
      (node (ref "U$35") (pin "1") (pinfunction "+_1") (pintype "bidirectional"))
      (node (ref "U$36") (pin "1") (pinfunction "+_1") (pintype "bidirectional"))
      (node (ref "U$37") (pin "1") (pinfunction "+_1") (pintype "bidirectional"))
      (node (ref "U$38") (pin "1") (pinfunction "+_1") (pintype "bidirectional"))
      (node (ref "U$39") (pin "1") (pinfunction "+_1") (pintype "bidirectional"))
      (node (ref "U$4") (pin "1") (pinfunction "NC1_1") (pintype "bidirectional"))
      (node (ref "U$4") (pin "3") (pinfunction "GND_3") (pintype "bidirectional"))
      (node (ref "U$4") (pin "8") (pinfunction "NC2_8") (pintype "bidirectional"))
      (node (ref "U$40") (pin "1") (pinfunction "NC1_1") (pintype "bidirectional"))
      (node (ref "U$40") (pin "3") (pinfunction "GND_3") (pintype "bidirectional"))
      (node (ref "U$40") (pin "8") (pinfunction "NC2_8") (pintype "bidirectional"))
      (node (ref "U$41") (pin "13") (pinfunction "OE_13") (pintype "bidirectional"))
      (node (ref "U$41") (pin "8") (pinfunction "GND_8") (pintype "bidirectional"))
      (node (ref "U$42") (pin "1") (pinfunction "NC1_1") (pintype "bidirectional"))
      (node (ref "U$42") (pin "3") (pinfunction "GND_3") (pintype "bidirectional"))
      (node (ref "U$42") (pin "8") (pinfunction "NC2_8") (pintype "bidirectional"))
      (node (ref "U$43") (pin "1") (pinfunction "NC1_1") (pintype "bidirectional"))
      (node (ref "U$43") (pin "3") (pinfunction "GND_3") (pintype "bidirectional"))
      (node (ref "U$43") (pin "8") (pinfunction "NC2_8") (pintype "bidirectional"))
      (node (ref "U$44") (pin "1") (pinfunction "NC1_1") (pintype "bidirectional"))
      (node (ref "U$44") (pin "3") (pinfunction "GND_3") (pintype "bidirectional"))
      (node (ref "U$44") (pin "8") (pinfunction "NC2_8") (pintype "bidirectional"))
      (node (ref "U$45") (pin "1") (pinfunction "+_1") (pintype "bidirectional"))
      (node (ref "U$46") (pin "1") (pinfunction "+_1") (pintype "bidirectional"))
      (node (ref "U$47") (pin "1") (pinfunction "+_1") (pintype "bidirectional"))
      (node (ref "U$48") (pin "1") (pinfunction "+_1") (pintype "bidirectional"))
      (node (ref "U$49") (pin "1") (pinfunction "+_1") (pintype "bidirectional"))
      (node (ref "U$5") (pin "1") (pinfunction "NC1_1") (pintype "bidirectional"))
      (node (ref "U$5") (pin "3") (pinfunction "GND_3") (pintype "bidirectional"))
      (node (ref "U$5") (pin "8") (pinfunction "NC2_8") (pintype "bidirectional"))
      (node (ref "U$50") (pin "1") (pinfunction "+_1") (pintype "bidirectional"))
      (node (ref "U$51") (pin "1") (pinfunction "+_1") (pintype "bidirectional"))
      (node (ref "U$52") (pin "1") (pinfunction "+_1") (pintype "bidirectional"))
      (node (ref "U$53") (pin "1") (pinfunction "NC1_1") (pintype "bidirectional"))
      (node (ref "U$53") (pin "3") (pinfunction "GND_3") (pintype "bidirectional"))
      (node (ref "U$53") (pin "8") (pinfunction "NC2_8") (pintype "bidirectional"))
      (node (ref "U$54") (pin "13") (pinfunction "OE_13") (pintype "bidirectional"))
      (node (ref "U$54") (pin "8") (pinfunction "GND_8") (pintype "bidirectional"))
      (node (ref "U$55") (pin "1") (pinfunction "NC1_1") (pintype "bidirectional"))
      (node (ref "U$55") (pin "3") (pinfunction "GND_3") (pintype "bidirectional"))
      (node (ref "U$55") (pin "8") (pinfunction "NC2_8") (pintype "bidirectional"))
      (node (ref "U$56") (pin "1") (pinfunction "NC1_1") (pintype "bidirectional"))
      (node (ref "U$56") (pin "3") (pinfunction "GND_3") (pintype "bidirectional"))
      (node (ref "U$56") (pin "8") (pinfunction "NC2_8") (pintype "bidirectional"))
      (node (ref "U$57") (pin "1") (pinfunction "NC1_1") (pintype "bidirectional"))
      (node (ref "U$57") (pin "3") (pinfunction "GND_3") (pintype "bidirectional"))
      (node (ref "U$57") (pin "8") (pinfunction "NC2_8") (pintype "bidirectional"))
      (node (ref "U$58") (pin "1") (pinfunction "+_1") (pintype "bidirectional"))
      (node (ref "U$59") (pin "1") (pinfunction "+_1") (pintype "bidirectional"))
      (node (ref "U$6") (pin "1") (pinfunction "+_1") (pintype "bidirectional"))
      (node (ref "U$60") (pin "1") (pinfunction "+_1") (pintype "bidirectional"))
      (node (ref "U$61") (pin "1") (pinfunction "+_1") (pintype "bidirectional"))
      (node (ref "U$62") (pin "1") (pinfunction "+_1") (pintype "bidirectional"))
      (node (ref "U$63") (pin "1") (pinfunction "+_1") (pintype "bidirectional"))
      (node (ref "U$64") (pin "1") (pinfunction "+_1") (pintype "bidirectional"))
      (node (ref "U$65") (pin "1") (pinfunction "+_1") (pintype "bidirectional"))
      (node (ref "U$66") (pin "1") (pinfunction "NC1_1") (pintype "bidirectional"))
      (node (ref "U$66") (pin "3") (pinfunction "GND_3") (pintype "bidirectional"))
      (node (ref "U$66") (pin "8") (pinfunction "NC2_8") (pintype "bidirectional"))
      (node (ref "U$67") (pin "13") (pinfunction "OE_13") (pintype "bidirectional"))
      (node (ref "U$67") (pin "8") (pinfunction "GND_8") (pintype "bidirectional"))
      (node (ref "U$68") (pin "1") (pinfunction "NC1_1") (pintype "bidirectional"))
      (node (ref "U$68") (pin "3") (pinfunction "GND_3") (pintype "bidirectional"))
      (node (ref "U$68") (pin "8") (pinfunction "NC2_8") (pintype "bidirectional"))
      (node (ref "U$69") (pin "1") (pinfunction "NC1_1") (pintype "bidirectional"))
      (node (ref "U$69") (pin "3") (pinfunction "GND_3") (pintype "bidirectional"))
      (node (ref "U$69") (pin "8") (pinfunction "NC2_8") (pintype "bidirectional"))
      (node (ref "U$7") (pin "1") (pinfunction "+_1") (pintype "bidirectional"))
      (node (ref "U$70") (pin "1") (pinfunction "NC1_1") (pintype "bidirectional"))
      (node (ref "U$70") (pin "3") (pinfunction "GND_3") (pintype "bidirectional"))
      (node (ref "U$70") (pin "8") (pinfunction "NC2_8") (pintype "bidirectional"))
      (node (ref "U$71") (pin "1") (pinfunction "+_1") (pintype "bidirectional"))
      (node (ref "U$72") (pin "1") (pinfunction "+_1") (pintype "bidirectional"))
      (node (ref "U$73") (pin "1") (pinfunction "+_1") (pintype "bidirectional"))
      (node (ref "U$74") (pin "1") (pinfunction "+_1") (pintype "bidirectional"))
      (node (ref "U$75") (pin "1") (pinfunction "+_1") (pintype "bidirectional"))
      (node (ref "U$76") (pin "1") (pinfunction "+_1") (pintype "bidirectional"))
      (node (ref "U$77") (pin "1") (pinfunction "+_1") (pintype "bidirectional"))
      (node (ref "U$78") (pin "1") (pinfunction "+_1") (pintype "bidirectional"))
      (node (ref "U$79") (pin "1") (pinfunction "NC1_1") (pintype "bidirectional"))
      (node (ref "U$79") (pin "3") (pinfunction "GND_3") (pintype "bidirectional"))
      (node (ref "U$79") (pin "8") (pinfunction "NC2_8") (pintype "bidirectional"))
      (node (ref "U$8") (pin "1") (pinfunction "+_1") (pintype "bidirectional"))
      (node (ref "U$80") (pin "13") (pinfunction "OE_13") (pintype "bidirectional"))
      (node (ref "U$80") (pin "8") (pinfunction "GND_8") (pintype "bidirectional"))
      (node (ref "U$81") (pin "1") (pinfunction "NC1_1") (pintype "bidirectional"))
      (node (ref "U$81") (pin "3") (pinfunction "GND_3") (pintype "bidirectional"))
      (node (ref "U$81") (pin "8") (pinfunction "NC2_8") (pintype "bidirectional"))
      (node (ref "U$82") (pin "1") (pinfunction "NC1_1") (pintype "bidirectional"))
      (node (ref "U$82") (pin "3") (pinfunction "GND_3") (pintype "bidirectional"))
      (node (ref "U$82") (pin "8") (pinfunction "NC2_8") (pintype "bidirectional"))
      (node (ref "U$83") (pin "1") (pinfunction "NC1_1") (pintype "bidirectional"))
      (node (ref "U$83") (pin "3") (pinfunction "GND_3") (pintype "bidirectional"))
      (node (ref "U$83") (pin "8") (pinfunction "NC2_8") (pintype "bidirectional"))
      (node (ref "U$84") (pin "1") (pinfunction "+_1") (pintype "bidirectional"))
      (node (ref "U$85") (pin "1") (pinfunction "+_1") (pintype "bidirectional"))
      (node (ref "U$86") (pin "1") (pinfunction "+_1") (pintype "bidirectional"))
      (node (ref "U$87") (pin "1") (pinfunction "+_1") (pintype "bidirectional"))
      (node (ref "U$88") (pin "1") (pinfunction "+_1") (pintype "bidirectional"))
      (node (ref "U$89") (pin "1") (pinfunction "+_1") (pintype "bidirectional"))
      (node (ref "U$9") (pin "1") (pinfunction "+_1") (pintype "bidirectional"))
      (node (ref "U$90") (pin "1") (pinfunction "+_1") (pintype "bidirectional"))
      (node (ref "U$91") (pin "1") (pinfunction "+_1") (pintype "bidirectional"))
      (node (ref "U$92") (pin "1") (pinfunction "NC1_1") (pintype "bidirectional"))
      (node (ref "U$92") (pin "3") (pinfunction "GND_3") (pintype "bidirectional"))
      (node (ref "U$92") (pin "8") (pinfunction "NC2_8") (pintype "bidirectional"))
      (node (ref "U$93") (pin "13") (pinfunction "OE_13") (pintype "bidirectional"))
      (node (ref "U$93") (pin "8") (pinfunction "GND_8") (pintype "bidirectional"))
      (node (ref "U$94") (pin "1") (pinfunction "NC1_1") (pintype "bidirectional"))
      (node (ref "U$94") (pin "3") (pinfunction "GND_3") (pintype "bidirectional"))
      (node (ref "U$94") (pin "8") (pinfunction "NC2_8") (pintype "bidirectional"))
      (node (ref "U$95") (pin "1") (pinfunction "NC1_1") (pintype "bidirectional"))
      (node (ref "U$95") (pin "3") (pinfunction "GND_3") (pintype "bidirectional"))
      (node (ref "U$95") (pin "8") (pinfunction "NC2_8") (pintype "bidirectional"))
      (node (ref "U$96") (pin "1") (pinfunction "NC1_1") (pintype "bidirectional"))
      (node (ref "U$96") (pin "3") (pinfunction "GND_3") (pintype "bidirectional"))
      (node (ref "U$96") (pin "8") (pinfunction "NC2_8") (pintype "bidirectional"))
      (node (ref "U$97") (pin "1") (pinfunction "+_1") (pintype "bidirectional"))
      (node (ref "U$98") (pin "1") (pinfunction "+_1") (pintype "bidirectional"))
      (node (ref "U$99") (pin "1") (pinfunction "+_1") (pintype "bidirectional"))
    )
    (net (code "2") (name "Net-(CONTROLA-KL)") (class "Default")
      (node (ref "CONTROL") (pin "1") (pinfunction "KL_1") (pintype "passive"))
      (node (ref "U$15") (pin "11") (pinfunction "CLOCK_11") (pintype "bidirectional"))
      (node (ref "U$2") (pin "11") (pinfunction "CLOCK_11") (pintype "bidirectional"))
      (node (ref "U$28") (pin "11") (pinfunction "CLOCK_11") (pintype "bidirectional"))
      (node (ref "U$41") (pin "11") (pinfunction "CLOCK_11") (pintype "bidirectional"))
      (node (ref "U$54") (pin "11") (pinfunction "CLOCK_11") (pintype "bidirectional"))
      (node (ref "U$67") (pin "11") (pinfunction "CLOCK_11") (pintype "bidirectional"))
      (node (ref "U$80") (pin "11") (pinfunction "CLOCK_11") (pintype "bidirectional"))
      (node (ref "U$93") (pin "11") (pinfunction "CLOCK_11") (pintype "bidirectional"))
    )
    (net (code "3") (name "Net-(CONTROLB-KL)") (class "Default")
      (node (ref "CONTROL") (pin "2") (pinfunction "KL_2") (pintype "passive"))
      (node (ref "U$15") (pin "12") (pinfunction "LATCH_12") (pintype "bidirectional"))
      (node (ref "U$2") (pin "12") (pinfunction "LATCH_12") (pintype "bidirectional"))
      (node (ref "U$28") (pin "12") (pinfunction "LATCH_12") (pintype "bidirectional"))
      (node (ref "U$41") (pin "12") (pinfunction "LATCH_12") (pintype "bidirectional"))
      (node (ref "U$54") (pin "12") (pinfunction "LATCH_12") (pintype "bidirectional"))
      (node (ref "U$67") (pin "12") (pinfunction "LATCH_12") (pintype "bidirectional"))
      (node (ref "U$80") (pin "12") (pinfunction "LATCH_12") (pintype "bidirectional"))
      (node (ref "U$93") (pin "12") (pinfunction "LATCH_12") (pintype "bidirectional"))
    )
    (net (code "4") (name "Net-(REGA-KL)") (class "Default")
      (node (ref "REG") (pin "1") (pinfunction "KL_1") (pintype "passive"))
      (node (ref "U$2") (pin "14") (pinfunction "DATA_14") (pintype "bidirectional"))
    )
    (net (code "5") (name "Net-(REGB-KL)") (class "Default")
      (node (ref "REG") (pin "2") (pinfunction "KL_2") (pintype "passive"))
      (node (ref "U$15") (pin "14") (pinfunction "DATA_14") (pintype "bidirectional"))
    )
    (net (code "6") (name "Net-(REGC-KL)") (class "Default")
      (node (ref "REG") (pin "3") (pinfunction "KL_3") (pintype "passive"))
      (node (ref "U$28") (pin "14") (pinfunction "DATA_14") (pintype "bidirectional"))
    )
    (net (code "7") (name "Net-(REGD-KL)") (class "Default")
      (node (ref "REG") (pin "4") (pinfunction "KL_4") (pintype "passive"))
      (node (ref "U$41") (pin "14") (pinfunction "DATA_14") (pintype "bidirectional"))
    )
    (net (code "8") (name "Net-(REGE-KL)") (class "Default")
      (node (ref "REG") (pin "5") (pinfunction "KL_5") (pintype "passive"))
      (node (ref "U$54") (pin "14") (pinfunction "DATA_14") (pintype "bidirectional"))
    )
    (net (code "9") (name "Net-(REGF-KL)") (class "Default")
      (node (ref "REG") (pin "6") (pinfunction "KL_6") (pintype "passive"))
      (node (ref "U$67") (pin "14") (pinfunction "DATA_14") (pintype "bidirectional"))
    )
    (net (code "10") (name "Net-(REGG-KL)") (class "Default")
      (node (ref "REG") (pin "7") (pinfunction "KL_7") (pintype "passive"))
      (node (ref "U$80") (pin "14") (pinfunction "DATA_14") (pintype "bidirectional"))
    )
    (net (code "11") (name "Net-(REGH-KL)") (class "Default")
      (node (ref "REG") (pin "8") (pinfunction "KL_8") (pintype "passive"))
      (node (ref "U$93") (pin "14") (pinfunction "DATA_14") (pintype "bidirectional"))
    )
    (net (code "12") (name "Net-(U$1-IN_A)") (class "Default")
      (node (ref "U$1") (pin "2") (pinfunction "IN_A_2") (pintype "bidirectional"))
      (node (ref "U$2") (pin "15") (pinfunction "Q0_15") (pintype "bidirectional"))
    )
    (net (code "13") (name "Net-(U$1-IN_B)") (class "Default")
      (node (ref "U$1") (pin "4") (pinfunction "IN_B_4") (pintype "bidirectional"))
      (node (ref "U$2") (pin "1") (pinfunction "Q1_1") (pintype "bidirectional"))
    )
    (net (code "14") (name "Net-(U$1-OUT_A)") (class "Default")
      (node (ref "U$1") (pin "7") (pinfunction "OUT_A_7") (pintype "bidirectional"))
      (node (ref "U$6") (pin "2") (pinfunction "-_2") (pintype "bidirectional"))
    )
    (net (code "15") (name "Net-(U$1-OUT_B)") (class "Default")
      (node (ref "U$1") (pin "5") (pinfunction "OUT_B_5") (pintype "bidirectional"))
      (node (ref "U$7") (pin "2") (pinfunction "-_2") (pintype "bidirectional"))
    )
    (net (code "16") (name "Net-(U$2-Q2)") (class "Default")
      (node (ref "U$2") (pin "2") (pinfunction "Q2_2") (pintype "bidirectional"))
      (node (ref "U$3") (pin "2") (pinfunction "IN_A_2") (pintype "bidirectional"))
    )
    (net (code "17") (name "Net-(U$2-Q3)") (class "Default")
      (node (ref "U$2") (pin "3") (pinfunction "Q3_3") (pintype "bidirectional"))
      (node (ref "U$3") (pin "4") (pinfunction "IN_B_4") (pintype "bidirectional"))
    )
    (net (code "18") (name "Net-(U$2-Q4)") (class "Default")
      (node (ref "U$2") (pin "4") (pinfunction "Q4_4") (pintype "bidirectional"))
      (node (ref "U$4") (pin "2") (pinfunction "IN_A_2") (pintype "bidirectional"))
    )
    (net (code "19") (name "Net-(U$2-Q5)") (class "Default")
      (node (ref "U$2") (pin "5") (pinfunction "Q5_5") (pintype "bidirectional"))
      (node (ref "U$4") (pin "4") (pinfunction "IN_B_4") (pintype "bidirectional"))
    )
    (net (code "20") (name "Net-(U$2-Q6)") (class "Default")
      (node (ref "U$2") (pin "6") (pinfunction "Q6_6") (pintype "bidirectional"))
      (node (ref "U$5") (pin "2") (pinfunction "IN_A_2") (pintype "bidirectional"))
    )
    (net (code "21") (name "Net-(U$2-Q7)") (class "Default")
      (node (ref "U$2") (pin "7") (pinfunction "Q7_7") (pintype "bidirectional"))
      (node (ref "U$5") (pin "4") (pinfunction "IN_B_4") (pintype "bidirectional"))
    )
    (net (code "22") (name "Net-(U$3-OUT_A)") (class "Default")
      (node (ref "U$3") (pin "7") (pinfunction "OUT_A_7") (pintype "bidirectional"))
      (node (ref "U$8") (pin "2") (pinfunction "-_2") (pintype "bidirectional"))
    )
    (net (code "23") (name "Net-(U$3-OUT_B)") (class "Default")
      (node (ref "U$3") (pin "5") (pinfunction "OUT_B_5") (pintype "bidirectional"))
      (node (ref "U$9") (pin "2") (pinfunction "-_2") (pintype "bidirectional"))
    )
    (net (code "24") (name "Net-(U$10--)") (class "Default")
      (node (ref "U$10") (pin "2") (pinfunction "-_2") (pintype "bidirectional"))
      (node (ref "U$4") (pin "7") (pinfunction "OUT_A_7") (pintype "bidirectional"))
    )
    (net (code "25") (name "Net-(U$11--)") (class "Default")
      (node (ref "U$11") (pin "2") (pinfunction "-_2") (pintype "bidirectional"))
      (node (ref "U$4") (pin "5") (pinfunction "OUT_B_5") (pintype "bidirectional"))
    )
    (net (code "26") (name "Net-(U$12--)") (class "Default")
      (node (ref "U$12") (pin "2") (pinfunction "-_2") (pintype "bidirectional"))
      (node (ref "U$5") (pin "7") (pinfunction "OUT_A_7") (pintype "bidirectional"))
    )
    (net (code "27") (name "Net-(U$13--)") (class "Default")
      (node (ref "U$13") (pin "2") (pinfunction "-_2") (pintype "bidirectional"))
      (node (ref "U$5") (pin "5") (pinfunction "OUT_B_5") (pintype "bidirectional"))
    )
    (net (code "28") (name "Net-(U$14-IN_A)") (class "Default")
      (node (ref "U$14") (pin "2") (pinfunction "IN_A_2") (pintype "bidirectional"))
      (node (ref "U$15") (pin "15") (pinfunction "Q0_15") (pintype "bidirectional"))
    )
    (net (code "29") (name "Net-(U$14-IN_B)") (class "Default")
      (node (ref "U$14") (pin "4") (pinfunction "IN_B_4") (pintype "bidirectional"))
      (node (ref "U$15") (pin "1") (pinfunction "Q1_1") (pintype "bidirectional"))
    )
    (net (code "30") (name "Net-(U$14-OUT_A)") (class "Default")
      (node (ref "U$14") (pin "7") (pinfunction "OUT_A_7") (pintype "bidirectional"))
      (node (ref "U$19") (pin "2") (pinfunction "-_2") (pintype "bidirectional"))
    )
    (net (code "31") (name "Net-(U$14-OUT_B)") (class "Default")
      (node (ref "U$14") (pin "5") (pinfunction "OUT_B_5") (pintype "bidirectional"))
      (node (ref "U$20") (pin "2") (pinfunction "-_2") (pintype "bidirectional"))
    )
    (net (code "32") (name "Net-(U$15-Q2)") (class "Default")
      (node (ref "U$15") (pin "2") (pinfunction "Q2_2") (pintype "bidirectional"))
      (node (ref "U$16") (pin "2") (pinfunction "IN_A_2") (pintype "bidirectional"))
    )
    (net (code "33") (name "Net-(U$15-Q3)") (class "Default")
      (node (ref "U$15") (pin "3") (pinfunction "Q3_3") (pintype "bidirectional"))
      (node (ref "U$16") (pin "4") (pinfunction "IN_B_4") (pintype "bidirectional"))
    )
    (net (code "34") (name "Net-(U$15-Q4)") (class "Default")
      (node (ref "U$15") (pin "4") (pinfunction "Q4_4") (pintype "bidirectional"))
      (node (ref "U$17") (pin "2") (pinfunction "IN_A_2") (pintype "bidirectional"))
    )
    (net (code "35") (name "Net-(U$15-Q5)") (class "Default")
      (node (ref "U$15") (pin "5") (pinfunction "Q5_5") (pintype "bidirectional"))
      (node (ref "U$17") (pin "4") (pinfunction "IN_B_4") (pintype "bidirectional"))
    )
    (net (code "36") (name "Net-(U$15-Q6)") (class "Default")
      (node (ref "U$15") (pin "6") (pinfunction "Q6_6") (pintype "bidirectional"))
      (node (ref "U$18") (pin "2") (pinfunction "IN_A_2") (pintype "bidirectional"))
    )
    (net (code "37") (name "Net-(U$15-Q7)") (class "Default")
      (node (ref "U$15") (pin "7") (pinfunction "Q7_7") (pintype "bidirectional"))
      (node (ref "U$18") (pin "4") (pinfunction "IN_B_4") (pintype "bidirectional"))
    )
    (net (code "38") (name "Net-(U$16-OUT_A)") (class "Default")
      (node (ref "U$16") (pin "7") (pinfunction "OUT_A_7") (pintype "bidirectional"))
      (node (ref "U$21") (pin "2") (pinfunction "-_2") (pintype "bidirectional"))
    )
    (net (code "39") (name "Net-(U$16-OUT_B)") (class "Default")
      (node (ref "U$16") (pin "5") (pinfunction "OUT_B_5") (pintype "bidirectional"))
      (node (ref "U$22") (pin "2") (pinfunction "-_2") (pintype "bidirectional"))
    )
    (net (code "40") (name "Net-(U$17-OUT_A)") (class "Default")
      (node (ref "U$17") (pin "7") (pinfunction "OUT_A_7") (pintype "bidirectional"))
      (node (ref "U$23") (pin "2") (pinfunction "-_2") (pintype "bidirectional"))
    )
    (net (code "41") (name "Net-(U$17-OUT_B)") (class "Default")
      (node (ref "U$17") (pin "5") (pinfunction "OUT_B_5") (pintype "bidirectional"))
      (node (ref "U$24") (pin "2") (pinfunction "-_2") (pintype "bidirectional"))
    )
    (net (code "42") (name "Net-(U$18-OUT_A)") (class "Default")
      (node (ref "U$18") (pin "7") (pinfunction "OUT_A_7") (pintype "bidirectional"))
      (node (ref "U$25") (pin "2") (pinfunction "-_2") (pintype "bidirectional"))
    )
    (net (code "43") (name "Net-(U$18-OUT_B)") (class "Default")
      (node (ref "U$18") (pin "5") (pinfunction "OUT_B_5") (pintype "bidirectional"))
      (node (ref "U$26") (pin "2") (pinfunction "-_2") (pintype "bidirectional"))
    )
    (net (code "44") (name "Net-(U$27-IN_A)") (class "Default")
      (node (ref "U$27") (pin "2") (pinfunction "IN_A_2") (pintype "bidirectional"))
      (node (ref "U$28") (pin "15") (pinfunction "Q0_15") (pintype "bidirectional"))
    )
    (net (code "45") (name "Net-(U$27-IN_B)") (class "Default")
      (node (ref "U$27") (pin "4") (pinfunction "IN_B_4") (pintype "bidirectional"))
      (node (ref "U$28") (pin "1") (pinfunction "Q1_1") (pintype "bidirectional"))
    )
    (net (code "46") (name "Net-(U$27-OUT_A)") (class "Default")
      (node (ref "U$27") (pin "7") (pinfunction "OUT_A_7") (pintype "bidirectional"))
      (node (ref "U$32") (pin "2") (pinfunction "-_2") (pintype "bidirectional"))
    )
    (net (code "47") (name "Net-(U$27-OUT_B)") (class "Default")
      (node (ref "U$27") (pin "5") (pinfunction "OUT_B_5") (pintype "bidirectional"))
      (node (ref "U$33") (pin "2") (pinfunction "-_2") (pintype "bidirectional"))
    )
    (net (code "48") (name "Net-(U$28-Q2)") (class "Default")
      (node (ref "U$28") (pin "2") (pinfunction "Q2_2") (pintype "bidirectional"))
      (node (ref "U$29") (pin "2") (pinfunction "IN_A_2") (pintype "bidirectional"))
    )
    (net (code "49") (name "Net-(U$28-Q3)") (class "Default")
      (node (ref "U$28") (pin "3") (pinfunction "Q3_3") (pintype "bidirectional"))
      (node (ref "U$29") (pin "4") (pinfunction "IN_B_4") (pintype "bidirectional"))
    )
    (net (code "50") (name "Net-(U$28-Q4)") (class "Default")
      (node (ref "U$28") (pin "4") (pinfunction "Q4_4") (pintype "bidirectional"))
      (node (ref "U$30") (pin "2") (pinfunction "IN_A_2") (pintype "bidirectional"))
    )
    (net (code "51") (name "Net-(U$28-Q5)") (class "Default")
      (node (ref "U$28") (pin "5") (pinfunction "Q5_5") (pintype "bidirectional"))
      (node (ref "U$30") (pin "4") (pinfunction "IN_B_4") (pintype "bidirectional"))
    )
    (net (code "52") (name "Net-(U$28-Q6)") (class "Default")
      (node (ref "U$28") (pin "6") (pinfunction "Q6_6") (pintype "bidirectional"))
      (node (ref "U$31") (pin "2") (pinfunction "IN_A_2") (pintype "bidirectional"))
    )
    (net (code "53") (name "Net-(U$28-Q7)") (class "Default")
      (node (ref "U$28") (pin "7") (pinfunction "Q7_7") (pintype "bidirectional"))
      (node (ref "U$31") (pin "4") (pinfunction "IN_B_4") (pintype "bidirectional"))
    )
    (net (code "54") (name "Net-(U$29-OUT_A)") (class "Default")
      (node (ref "U$29") (pin "7") (pinfunction "OUT_A_7") (pintype "bidirectional"))
      (node (ref "U$34") (pin "2") (pinfunction "-_2") (pintype "bidirectional"))
    )
    (net (code "55") (name "Net-(U$29-OUT_B)") (class "Default")
      (node (ref "U$29") (pin "5") (pinfunction "OUT_B_5") (pintype "bidirectional"))
      (node (ref "U$35") (pin "2") (pinfunction "-_2") (pintype "bidirectional"))
    )
    (net (code "56") (name "Net-(U$30-OUT_A)") (class "Default")
      (node (ref "U$30") (pin "7") (pinfunction "OUT_A_7") (pintype "bidirectional"))
      (node (ref "U$36") (pin "2") (pinfunction "-_2") (pintype "bidirectional"))
    )
    (net (code "57") (name "Net-(U$30-OUT_B)") (class "Default")
      (node (ref "U$30") (pin "5") (pinfunction "OUT_B_5") (pintype "bidirectional"))
      (node (ref "U$37") (pin "2") (pinfunction "-_2") (pintype "bidirectional"))
    )
    (net (code "58") (name "Net-(U$31-OUT_A)") (class "Default")
      (node (ref "U$31") (pin "7") (pinfunction "OUT_A_7") (pintype "bidirectional"))
      (node (ref "U$38") (pin "2") (pinfunction "-_2") (pintype "bidirectional"))
    )
    (net (code "59") (name "Net-(U$31-OUT_B)") (class "Default")
      (node (ref "U$31") (pin "5") (pinfunction "OUT_B_5") (pintype "bidirectional"))
      (node (ref "U$39") (pin "2") (pinfunction "-_2") (pintype "bidirectional"))
    )
    (net (code "60") (name "Net-(U$40-IN_A)") (class "Default")
      (node (ref "U$40") (pin "2") (pinfunction "IN_A_2") (pintype "bidirectional"))
      (node (ref "U$41") (pin "15") (pinfunction "Q0_15") (pintype "bidirectional"))
    )
    (net (code "61") (name "Net-(U$40-IN_B)") (class "Default")
      (node (ref "U$40") (pin "4") (pinfunction "IN_B_4") (pintype "bidirectional"))
      (node (ref "U$41") (pin "1") (pinfunction "Q1_1") (pintype "bidirectional"))
    )
    (net (code "62") (name "Net-(U$40-OUT_A)") (class "Default")
      (node (ref "U$40") (pin "7") (pinfunction "OUT_A_7") (pintype "bidirectional"))
      (node (ref "U$45") (pin "2") (pinfunction "-_2") (pintype "bidirectional"))
    )
    (net (code "63") (name "Net-(U$40-OUT_B)") (class "Default")
      (node (ref "U$40") (pin "5") (pinfunction "OUT_B_5") (pintype "bidirectional"))
      (node (ref "U$46") (pin "2") (pinfunction "-_2") (pintype "bidirectional"))
    )
    (net (code "64") (name "Net-(U$41-Q2)") (class "Default")
      (node (ref "U$41") (pin "2") (pinfunction "Q2_2") (pintype "bidirectional"))
      (node (ref "U$42") (pin "2") (pinfunction "IN_A_2") (pintype "bidirectional"))
    )
    (net (code "65") (name "Net-(U$41-Q3)") (class "Default")
      (node (ref "U$41") (pin "3") (pinfunction "Q3_3") (pintype "bidirectional"))
      (node (ref "U$42") (pin "4") (pinfunction "IN_B_4") (pintype "bidirectional"))
    )
    (net (code "66") (name "Net-(U$41-Q4)") (class "Default")
      (node (ref "U$41") (pin "4") (pinfunction "Q4_4") (pintype "bidirectional"))
      (node (ref "U$43") (pin "2") (pinfunction "IN_A_2") (pintype "bidirectional"))
    )
    (net (code "67") (name "Net-(U$41-Q5)") (class "Default")
      (node (ref "U$41") (pin "5") (pinfunction "Q5_5") (pintype "bidirectional"))
      (node (ref "U$43") (pin "4") (pinfunction "IN_B_4") (pintype "bidirectional"))
    )
    (net (code "68") (name "Net-(U$41-Q6)") (class "Default")
      (node (ref "U$41") (pin "6") (pinfunction "Q6_6") (pintype "bidirectional"))
      (node (ref "U$44") (pin "2") (pinfunction "IN_A_2") (pintype "bidirectional"))
    )
    (net (code "69") (name "Net-(U$41-Q7)") (class "Default")
      (node (ref "U$41") (pin "7") (pinfunction "Q7_7") (pintype "bidirectional"))
      (node (ref "U$44") (pin "4") (pinfunction "IN_B_4") (pintype "bidirectional"))
    )
    (net (code "70") (name "Net-(U$42-OUT_A)") (class "Default")
      (node (ref "U$42") (pin "7") (pinfunction "OUT_A_7") (pintype "bidirectional"))
      (node (ref "U$47") (pin "2") (pinfunction "-_2") (pintype "bidirectional"))
    )
    (net (code "71") (name "Net-(U$42-OUT_B)") (class "Default")
      (node (ref "U$42") (pin "5") (pinfunction "OUT_B_5") (pintype "bidirectional"))
      (node (ref "U$48") (pin "2") (pinfunction "-_2") (pintype "bidirectional"))
    )
    (net (code "72") (name "Net-(U$43-OUT_A)") (class "Default")
      (node (ref "U$43") (pin "7") (pinfunction "OUT_A_7") (pintype "bidirectional"))
      (node (ref "U$49") (pin "2") (pinfunction "-_2") (pintype "bidirectional"))
    )
    (net (code "73") (name "Net-(U$43-OUT_B)") (class "Default")
      (node (ref "U$43") (pin "5") (pinfunction "OUT_B_5") (pintype "bidirectional"))
      (node (ref "U$50") (pin "2") (pinfunction "-_2") (pintype "bidirectional"))
    )
    (net (code "74") (name "Net-(U$44-OUT_A)") (class "Default")
      (node (ref "U$44") (pin "7") (pinfunction "OUT_A_7") (pintype "bidirectional"))
      (node (ref "U$51") (pin "2") (pinfunction "-_2") (pintype "bidirectional"))
    )
    (net (code "75") (name "Net-(U$44-OUT_B)") (class "Default")
      (node (ref "U$44") (pin "5") (pinfunction "OUT_B_5") (pintype "bidirectional"))
      (node (ref "U$52") (pin "2") (pinfunction "-_2") (pintype "bidirectional"))
    )
    (net (code "76") (name "Net-(U$53-IN_A)") (class "Default")
      (node (ref "U$53") (pin "2") (pinfunction "IN_A_2") (pintype "bidirectional"))
      (node (ref "U$54") (pin "15") (pinfunction "Q0_15") (pintype "bidirectional"))
    )
    (net (code "77") (name "Net-(U$53-IN_B)") (class "Default")
      (node (ref "U$53") (pin "4") (pinfunction "IN_B_4") (pintype "bidirectional"))
      (node (ref "U$54") (pin "1") (pinfunction "Q1_1") (pintype "bidirectional"))
    )
    (net (code "78") (name "Net-(U$53-OUT_A)") (class "Default")
      (node (ref "U$53") (pin "7") (pinfunction "OUT_A_7") (pintype "bidirectional"))
      (node (ref "U$58") (pin "2") (pinfunction "-_2") (pintype "bidirectional"))
    )
    (net (code "79") (name "Net-(U$53-OUT_B)") (class "Default")
      (node (ref "U$53") (pin "5") (pinfunction "OUT_B_5") (pintype "bidirectional"))
      (node (ref "U$59") (pin "2") (pinfunction "-_2") (pintype "bidirectional"))
    )
    (net (code "80") (name "Net-(U$54-Q2)") (class "Default")
      (node (ref "U$54") (pin "2") (pinfunction "Q2_2") (pintype "bidirectional"))
      (node (ref "U$55") (pin "2") (pinfunction "IN_A_2") (pintype "bidirectional"))
    )
    (net (code "81") (name "Net-(U$54-Q3)") (class "Default")
      (node (ref "U$54") (pin "3") (pinfunction "Q3_3") (pintype "bidirectional"))
      (node (ref "U$55") (pin "4") (pinfunction "IN_B_4") (pintype "bidirectional"))
    )
    (net (code "82") (name "Net-(U$54-Q4)") (class "Default")
      (node (ref "U$54") (pin "4") (pinfunction "Q4_4") (pintype "bidirectional"))
      (node (ref "U$56") (pin "2") (pinfunction "IN_A_2") (pintype "bidirectional"))
    )
    (net (code "83") (name "Net-(U$54-Q5)") (class "Default")
      (node (ref "U$54") (pin "5") (pinfunction "Q5_5") (pintype "bidirectional"))
      (node (ref "U$56") (pin "4") (pinfunction "IN_B_4") (pintype "bidirectional"))
    )
    (net (code "84") (name "Net-(U$54-Q6)") (class "Default")
      (node (ref "U$54") (pin "6") (pinfunction "Q6_6") (pintype "bidirectional"))
      (node (ref "U$57") (pin "2") (pinfunction "IN_A_2") (pintype "bidirectional"))
    )
    (net (code "85") (name "Net-(U$54-Q7)") (class "Default")
      (node (ref "U$54") (pin "7") (pinfunction "Q7_7") (pintype "bidirectional"))
      (node (ref "U$57") (pin "4") (pinfunction "IN_B_4") (pintype "bidirectional"))
    )
    (net (code "86") (name "Net-(U$55-OUT_A)") (class "Default")
      (node (ref "U$55") (pin "7") (pinfunction "OUT_A_7") (pintype "bidirectional"))
      (node (ref "U$60") (pin "2") (pinfunction "-_2") (pintype "bidirectional"))
    )
    (net (code "87") (name "Net-(U$55-OUT_B)") (class "Default")
      (node (ref "U$55") (pin "5") (pinfunction "OUT_B_5") (pintype "bidirectional"))
      (node (ref "U$61") (pin "2") (pinfunction "-_2") (pintype "bidirectional"))
    )
    (net (code "88") (name "Net-(U$56-OUT_A)") (class "Default")
      (node (ref "U$56") (pin "7") (pinfunction "OUT_A_7") (pintype "bidirectional"))
      (node (ref "U$62") (pin "2") (pinfunction "-_2") (pintype "bidirectional"))
    )
    (net (code "89") (name "Net-(U$56-OUT_B)") (class "Default")
      (node (ref "U$56") (pin "5") (pinfunction "OUT_B_5") (pintype "bidirectional"))
      (node (ref "U$63") (pin "2") (pinfunction "-_2") (pintype "bidirectional"))
    )
    (net (code "90") (name "Net-(U$57-OUT_A)") (class "Default")
      (node (ref "U$57") (pin "7") (pinfunction "OUT_A_7") (pintype "bidirectional"))
      (node (ref "U$64") (pin "2") (pinfunction "-_2") (pintype "bidirectional"))
    )
    (net (code "91") (name "Net-(U$57-OUT_B)") (class "Default")
      (node (ref "U$57") (pin "5") (pinfunction "OUT_B_5") (pintype "bidirectional"))
      (node (ref "U$65") (pin "2") (pinfunction "-_2") (pintype "bidirectional"))
    )
    (net (code "92") (name "Net-(U$66-IN_A)") (class "Default")
      (node (ref "U$66") (pin "2") (pinfunction "IN_A_2") (pintype "bidirectional"))
      (node (ref "U$67") (pin "15") (pinfunction "Q0_15") (pintype "bidirectional"))
    )
    (net (code "93") (name "Net-(U$66-IN_B)") (class "Default")
      (node (ref "U$66") (pin "4") (pinfunction "IN_B_4") (pintype "bidirectional"))
      (node (ref "U$67") (pin "1") (pinfunction "Q1_1") (pintype "bidirectional"))
    )
    (net (code "94") (name "Net-(U$66-OUT_A)") (class "Default")
      (node (ref "U$66") (pin "7") (pinfunction "OUT_A_7") (pintype "bidirectional"))
      (node (ref "U$71") (pin "2") (pinfunction "-_2") (pintype "bidirectional"))
    )
    (net (code "95") (name "Net-(U$66-OUT_B)") (class "Default")
      (node (ref "U$66") (pin "5") (pinfunction "OUT_B_5") (pintype "bidirectional"))
      (node (ref "U$72") (pin "2") (pinfunction "-_2") (pintype "bidirectional"))
    )
    (net (code "96") (name "Net-(U$67-Q2)") (class "Default")
      (node (ref "U$67") (pin "2") (pinfunction "Q2_2") (pintype "bidirectional"))
      (node (ref "U$68") (pin "2") (pinfunction "IN_A_2") (pintype "bidirectional"))
    )
    (net (code "97") (name "Net-(U$67-Q3)") (class "Default")
      (node (ref "U$67") (pin "3") (pinfunction "Q3_3") (pintype "bidirectional"))
      (node (ref "U$68") (pin "4") (pinfunction "IN_B_4") (pintype "bidirectional"))
    )
    (net (code "98") (name "Net-(U$67-Q4)") (class "Default")
      (node (ref "U$67") (pin "4") (pinfunction "Q4_4") (pintype "bidirectional"))
      (node (ref "U$69") (pin "2") (pinfunction "IN_A_2") (pintype "bidirectional"))
    )
    (net (code "99") (name "Net-(U$67-Q5)") (class "Default")
      (node (ref "U$67") (pin "5") (pinfunction "Q5_5") (pintype "bidirectional"))
      (node (ref "U$69") (pin "4") (pinfunction "IN_B_4") (pintype "bidirectional"))
    )
    (net (code "100") (name "Net-(U$67-Q6)") (class "Default")
      (node (ref "U$67") (pin "6") (pinfunction "Q6_6") (pintype "bidirectional"))
      (node (ref "U$70") (pin "2") (pinfunction "IN_A_2") (pintype "bidirectional"))
    )
    (net (code "101") (name "Net-(U$67-Q7)") (class "Default")
      (node (ref "U$67") (pin "7") (pinfunction "Q7_7") (pintype "bidirectional"))
      (node (ref "U$70") (pin "4") (pinfunction "IN_B_4") (pintype "bidirectional"))
    )
    (net (code "102") (name "Net-(U$68-OUT_A)") (class "Default")
      (node (ref "U$68") (pin "7") (pinfunction "OUT_A_7") (pintype "bidirectional"))
      (node (ref "U$73") (pin "2") (pinfunction "-_2") (pintype "bidirectional"))
    )
    (net (code "103") (name "Net-(U$68-OUT_B)") (class "Default")
      (node (ref "U$68") (pin "5") (pinfunction "OUT_B_5") (pintype "bidirectional"))
      (node (ref "U$74") (pin "2") (pinfunction "-_2") (pintype "bidirectional"))
    )
    (net (code "104") (name "Net-(U$69-OUT_A)") (class "Default")
      (node (ref "U$69") (pin "7") (pinfunction "OUT_A_7") (pintype "bidirectional"))
      (node (ref "U$75") (pin "2") (pinfunction "-_2") (pintype "bidirectional"))
    )
    (net (code "105") (name "Net-(U$69-OUT_B)") (class "Default")
      (node (ref "U$69") (pin "5") (pinfunction "OUT_B_5") (pintype "bidirectional"))
      (node (ref "U$76") (pin "2") (pinfunction "-_2") (pintype "bidirectional"))
    )
    (net (code "106") (name "Net-(U$70-OUT_A)") (class "Default")
      (node (ref "U$70") (pin "7") (pinfunction "OUT_A_7") (pintype "bidirectional"))
      (node (ref "U$77") (pin "2") (pinfunction "-_2") (pintype "bidirectional"))
    )
    (net (code "107") (name "Net-(U$70-OUT_B)") (class "Default")
      (node (ref "U$70") (pin "5") (pinfunction "OUT_B_5") (pintype "bidirectional"))
      (node (ref "U$78") (pin "2") (pinfunction "-_2") (pintype "bidirectional"))
    )
    (net (code "108") (name "Net-(U$79-IN_A)") (class "Default")
      (node (ref "U$79") (pin "2") (pinfunction "IN_A_2") (pintype "bidirectional"))
      (node (ref "U$80") (pin "15") (pinfunction "Q0_15") (pintype "bidirectional"))
    )
    (net (code "109") (name "Net-(U$79-IN_B)") (class "Default")
      (node (ref "U$79") (pin "4") (pinfunction "IN_B_4") (pintype "bidirectional"))
      (node (ref "U$80") (pin "1") (pinfunction "Q1_1") (pintype "bidirectional"))
    )
    (net (code "110") (name "Net-(U$79-OUT_A)") (class "Default")
      (node (ref "U$79") (pin "7") (pinfunction "OUT_A_7") (pintype "bidirectional"))
      (node (ref "U$84") (pin "2") (pinfunction "-_2") (pintype "bidirectional"))
    )
    (net (code "111") (name "Net-(U$79-OUT_B)") (class "Default")
      (node (ref "U$79") (pin "5") (pinfunction "OUT_B_5") (pintype "bidirectional"))
      (node (ref "U$85") (pin "2") (pinfunction "-_2") (pintype "bidirectional"))
    )
    (net (code "112") (name "Net-(U$80-Q2)") (class "Default")
      (node (ref "U$80") (pin "2") (pinfunction "Q2_2") (pintype "bidirectional"))
      (node (ref "U$81") (pin "2") (pinfunction "IN_A_2") (pintype "bidirectional"))
    )
    (net (code "113") (name "Net-(U$80-Q3)") (class "Default")
      (node (ref "U$80") (pin "3") (pinfunction "Q3_3") (pintype "bidirectional"))
      (node (ref "U$81") (pin "4") (pinfunction "IN_B_4") (pintype "bidirectional"))
    )
    (net (code "114") (name "Net-(U$80-Q4)") (class "Default")
      (node (ref "U$80") (pin "4") (pinfunction "Q4_4") (pintype "bidirectional"))
      (node (ref "U$82") (pin "2") (pinfunction "IN_A_2") (pintype "bidirectional"))
    )
    (net (code "115") (name "Net-(U$80-Q5)") (class "Default")
      (node (ref "U$80") (pin "5") (pinfunction "Q5_5") (pintype "bidirectional"))
      (node (ref "U$82") (pin "4") (pinfunction "IN_B_4") (pintype "bidirectional"))
    )
    (net (code "116") (name "Net-(U$80-Q6)") (class "Default")
      (node (ref "U$80") (pin "6") (pinfunction "Q6_6") (pintype "bidirectional"))
      (node (ref "U$83") (pin "2") (pinfunction "IN_A_2") (pintype "bidirectional"))
    )
    (net (code "117") (name "Net-(U$80-Q7)") (class "Default")
      (node (ref "U$80") (pin "7") (pinfunction "Q7_7") (pintype "bidirectional"))
      (node (ref "U$83") (pin "4") (pinfunction "IN_B_4") (pintype "bidirectional"))
    )
    (net (code "118") (name "Net-(U$81-OUT_A)") (class "Default")
      (node (ref "U$81") (pin "7") (pinfunction "OUT_A_7") (pintype "bidirectional"))
      (node (ref "U$86") (pin "2") (pinfunction "-_2") (pintype "bidirectional"))
    )
    (net (code "119") (name "Net-(U$81-OUT_B)") (class "Default")
      (node (ref "U$81") (pin "5") (pinfunction "OUT_B_5") (pintype "bidirectional"))
      (node (ref "U$87") (pin "2") (pinfunction "-_2") (pintype "bidirectional"))
    )
    (net (code "120") (name "Net-(U$82-OUT_A)") (class "Default")
      (node (ref "U$82") (pin "7") (pinfunction "OUT_A_7") (pintype "bidirectional"))
      (node (ref "U$88") (pin "2") (pinfunction "-_2") (pintype "bidirectional"))
    )
    (net (code "121") (name "Net-(U$82-OUT_B)") (class "Default")
      (node (ref "U$82") (pin "5") (pinfunction "OUT_B_5") (pintype "bidirectional"))
      (node (ref "U$89") (pin "2") (pinfunction "-_2") (pintype "bidirectional"))
    )
    (net (code "122") (name "Net-(U$83-OUT_A)") (class "Default")
      (node (ref "U$83") (pin "7") (pinfunction "OUT_A_7") (pintype "bidirectional"))
      (node (ref "U$90") (pin "2") (pinfunction "-_2") (pintype "bidirectional"))
    )
    (net (code "123") (name "Net-(U$83-OUT_B)") (class "Default")
      (node (ref "U$83") (pin "5") (pinfunction "OUT_B_5") (pintype "bidirectional"))
      (node (ref "U$91") (pin "2") (pinfunction "-_2") (pintype "bidirectional"))
    )
    (net (code "124") (name "Net-(U$92-IN_A)") (class "Default")
      (node (ref "U$92") (pin "2") (pinfunction "IN_A_2") (pintype "bidirectional"))
      (node (ref "U$93") (pin "15") (pinfunction "Q0_15") (pintype "bidirectional"))
    )
    (net (code "125") (name "Net-(U$92-IN_B)") (class "Default")
      (node (ref "U$92") (pin "4") (pinfunction "IN_B_4") (pintype "bidirectional"))
      (node (ref "U$93") (pin "1") (pinfunction "Q1_1") (pintype "bidirectional"))
    )
    (net (code "126") (name "Net-(U$92-OUT_A)") (class "Default")
      (node (ref "U$92") (pin "7") (pinfunction "OUT_A_7") (pintype "bidirectional"))
      (node (ref "U$97") (pin "2") (pinfunction "-_2") (pintype "bidirectional"))
    )
    (net (code "127") (name "Net-(U$92-OUT_B)") (class "Default")
      (node (ref "U$92") (pin "5") (pinfunction "OUT_B_5") (pintype "bidirectional"))
      (node (ref "U$98") (pin "2") (pinfunction "-_2") (pintype "bidirectional"))
    )
    (net (code "128") (name "Net-(U$93-Q2)") (class "Default")
      (node (ref "U$93") (pin "2") (pinfunction "Q2_2") (pintype "bidirectional"))
      (node (ref "U$94") (pin "2") (pinfunction "IN_A_2") (pintype "bidirectional"))
    )
    (net (code "129") (name "Net-(U$93-Q3)") (class "Default")
      (node (ref "U$93") (pin "3") (pinfunction "Q3_3") (pintype "bidirectional"))
      (node (ref "U$94") (pin "4") (pinfunction "IN_B_4") (pintype "bidirectional"))
    )
    (net (code "130") (name "Net-(U$93-Q4)") (class "Default")
      (node (ref "U$93") (pin "4") (pinfunction "Q4_4") (pintype "bidirectional"))
      (node (ref "U$95") (pin "2") (pinfunction "IN_A_2") (pintype "bidirectional"))
    )
    (net (code "131") (name "Net-(U$93-Q5)") (class "Default")
      (node (ref "U$93") (pin "5") (pinfunction "Q5_5") (pintype "bidirectional"))
      (node (ref "U$95") (pin "4") (pinfunction "IN_B_4") (pintype "bidirectional"))
    )
    (net (code "132") (name "Net-(U$93-Q6)") (class "Default")
      (node (ref "U$93") (pin "6") (pinfunction "Q6_6") (pintype "bidirectional"))
      (node (ref "U$96") (pin "2") (pinfunction "IN_A_2") (pintype "bidirectional"))
    )
    (net (code "133") (name "Net-(U$93-Q7)") (class "Default")
      (node (ref "U$93") (pin "7") (pinfunction "Q7_7") (pintype "bidirectional"))
      (node (ref "U$96") (pin "4") (pinfunction "IN_B_4") (pintype "bidirectional"))
    )
    (net (code "134") (name "Net-(U$94-OUT_A)") (class "Default")
      (node (ref "U$94") (pin "7") (pinfunction "OUT_A_7") (pintype "bidirectional"))
      (node (ref "U$99") (pin "2") (pinfunction "-_2") (pintype "bidirectional"))
    )
    (net (code "135") (name "Net-(U$100--)") (class "Default")
      (node (ref "U$100") (pin "2") (pinfunction "-_2") (pintype "bidirectional"))
      (node (ref "U$94") (pin "5") (pinfunction "OUT_B_5") (pintype "bidirectional"))
    )
    (net (code "136") (name "Net-(U$101--)") (class "Default")
      (node (ref "U$101") (pin "2") (pinfunction "-_2") (pintype "bidirectional"))
      (node (ref "U$95") (pin "7") (pinfunction "OUT_A_7") (pintype "bidirectional"))
    )
    (net (code "137") (name "Net-(U$102--)") (class "Default")
      (node (ref "U$102") (pin "2") (pinfunction "-_2") (pintype "bidirectional"))
      (node (ref "U$95") (pin "5") (pinfunction "OUT_B_5") (pintype "bidirectional"))
    )
    (net (code "138") (name "Net-(U$103--)") (class "Default")
      (node (ref "U$103") (pin "2") (pinfunction "-_2") (pintype "bidirectional"))
      (node (ref "U$96") (pin "7") (pinfunction "OUT_A_7") (pintype "bidirectional"))
    )
    (net (code "139") (name "Net-(U$104--)") (class "Default")
      (node (ref "U$104") (pin "2") (pinfunction "-_2") (pintype "bidirectional"))
      (node (ref "U$96") (pin "5") (pinfunction "OUT_B_5") (pintype "bidirectional"))
    )
    (net (code "140") (name "VCC +5v") (class "Default")
      (node (ref "C1") (pin "2") (pinfunction "2_2") (pintype "passive"))
      (node (ref "C11") (pin "2") (pinfunction "2_2") (pintype "passive"))
      (node (ref "C16") (pin "2") (pinfunction "2_2") (pintype "passive"))
      (node (ref "C21") (pin "2") (pinfunction "2_2") (pintype "passive"))
      (node (ref "C26") (pin "2") (pinfunction "2_2") (pintype "passive"))
      (node (ref "C31") (pin "2") (pinfunction "2_2") (pintype "passive"))
      (node (ref "C36") (pin "2") (pinfunction "2_2") (pintype "passive"))
      (node (ref "C6") (pin "2") (pinfunction "2_2") (pintype "passive"))
      (node (ref "POWER") (pin "3") (pinfunction "KL_3") (pintype "passive"))
      (node (ref "U$15") (pin "10") (pinfunction "MR_10") (pintype "bidirectional"))
      (node (ref "U$15") (pin "16") (pinfunction "VCC_16") (pintype "bidirectional"))
      (node (ref "U$2") (pin "10") (pinfunction "MR_10") (pintype "bidirectional"))
      (node (ref "U$2") (pin "16") (pinfunction "VCC_16") (pintype "bidirectional"))
      (node (ref "U$28") (pin "10") (pinfunction "MR_10") (pintype "bidirectional"))
      (node (ref "U$28") (pin "16") (pinfunction "VCC_16") (pintype "bidirectional"))
      (node (ref "U$41") (pin "10") (pinfunction "MR_10") (pintype "bidirectional"))
      (node (ref "U$41") (pin "16") (pinfunction "VCC_16") (pintype "bidirectional"))
      (node (ref "U$54") (pin "10") (pinfunction "MR_10") (pintype "bidirectional"))
      (node (ref "U$54") (pin "16") (pinfunction "VCC_16") (pintype "bidirectional"))
      (node (ref "U$67") (pin "10") (pinfunction "MR_10") (pintype "bidirectional"))
      (node (ref "U$67") (pin "16") (pinfunction "VCC_16") (pintype "bidirectional"))
      (node (ref "U$80") (pin "10") (pinfunction "MR_10") (pintype "bidirectional"))
      (node (ref "U$80") (pin "16") (pinfunction "VCC_16") (pintype "bidirectional"))
      (node (ref "U$93") (pin "10") (pinfunction "MR_10") (pintype "bidirectional"))
      (node (ref "U$93") (pin "16") (pinfunction "VCC_16") (pintype "bidirectional"))
    )
    (net (code "141") (name "VDD + 5-18V") (class "Default")
      (node (ref "C10") (pin "2") (pinfunction "2_2") (pintype "passive"))
      (node (ref "C12") (pin "2") (pinfunction "2_2") (pintype "passive"))
      (node (ref "C13") (pin "2") (pinfunction "2_2") (pintype "passive"))
      (node (ref "C14") (pin "2") (pinfunction "2_2") (pintype "passive"))
      (node (ref "C15") (pin "2") (pinfunction "2_2") (pintype "passive"))
      (node (ref "C17") (pin "2") (pinfunction "2_2") (pintype "passive"))
      (node (ref "C18") (pin "2") (pinfunction "2_2") (pintype "passive"))
      (node (ref "C19") (pin "2") (pinfunction "2_2") (pintype "passive"))
      (node (ref "C2") (pin "2") (pinfunction "2_2") (pintype "passive"))
      (node (ref "C20") (pin "2") (pinfunction "2_2") (pintype "passive"))
      (node (ref "C22") (pin "2") (pinfunction "2_2") (pintype "passive"))
      (node (ref "C23") (pin "2") (pinfunction "2_2") (pintype "passive"))
      (node (ref "C24") (pin "2") (pinfunction "2_2") (pintype "passive"))
      (node (ref "C25") (pin "2") (pinfunction "2_2") (pintype "passive"))
      (node (ref "C27") (pin "2") (pinfunction "2_2") (pintype "passive"))
      (node (ref "C28") (pin "2") (pinfunction "2_2") (pintype "passive"))
      (node (ref "C29") (pin "2") (pinfunction "2_2") (pintype "passive"))
      (node (ref "C3") (pin "2") (pinfunction "2_2") (pintype "passive"))
      (node (ref "C30") (pin "2") (pinfunction "2_2") (pintype "passive"))
      (node (ref "C32") (pin "2") (pinfunction "2_2") (pintype "passive"))
      (node (ref "C33") (pin "2") (pinfunction "2_2") (pintype "passive"))
      (node (ref "C34") (pin "2") (pinfunction "2_2") (pintype "passive"))
      (node (ref "C35") (pin "2") (pinfunction "2_2") (pintype "passive"))
      (node (ref "C37") (pin "2") (pinfunction "2_2") (pintype "passive"))
      (node (ref "C38") (pin "2") (pinfunction "2_2") (pintype "passive"))
      (node (ref "C39") (pin "2") (pinfunction "2_2") (pintype "passive"))
      (node (ref "C4") (pin "2") (pinfunction "2_2") (pintype "passive"))
      (node (ref "C40") (pin "2") (pinfunction "2_2") (pintype "passive"))
      (node (ref "C5") (pin "2") (pinfunction "2_2") (pintype "passive"))
      (node (ref "C7") (pin "2") (pinfunction "2_2") (pintype "passive"))
      (node (ref "C8") (pin "2") (pinfunction "2_2") (pintype "passive"))
      (node (ref "C9") (pin "2") (pinfunction "2_2") (pintype "passive"))
      (node (ref "POWER") (pin "1") (pinfunction "KL_1") (pintype "passive"))
      (node (ref "U$1") (pin "6") (pinfunction "VDD_6") (pintype "bidirectional"))
      (node (ref "U$14") (pin "6") (pinfunction "VDD_6") (pintype "bidirectional"))
      (node (ref "U$16") (pin "6") (pinfunction "VDD_6") (pintype "bidirectional"))
      (node (ref "U$17") (pin "6") (pinfunction "VDD_6") (pintype "bidirectional"))
      (node (ref "U$18") (pin "6") (pinfunction "VDD_6") (pintype "bidirectional"))
      (node (ref "U$27") (pin "6") (pinfunction "VDD_6") (pintype "bidirectional"))
      (node (ref "U$29") (pin "6") (pinfunction "VDD_6") (pintype "bidirectional"))
      (node (ref "U$3") (pin "6") (pinfunction "VDD_6") (pintype "bidirectional"))
      (node (ref "U$30") (pin "6") (pinfunction "VDD_6") (pintype "bidirectional"))
      (node (ref "U$31") (pin "6") (pinfunction "VDD_6") (pintype "bidirectional"))
      (node (ref "U$4") (pin "6") (pinfunction "VDD_6") (pintype "bidirectional"))
      (node (ref "U$40") (pin "6") (pinfunction "VDD_6") (pintype "bidirectional"))
      (node (ref "U$42") (pin "6") (pinfunction "VDD_6") (pintype "bidirectional"))
      (node (ref "U$43") (pin "6") (pinfunction "VDD_6") (pintype "bidirectional"))
      (node (ref "U$44") (pin "6") (pinfunction "VDD_6") (pintype "bidirectional"))
      (node (ref "U$5") (pin "6") (pinfunction "VDD_6") (pintype "bidirectional"))
      (node (ref "U$53") (pin "6") (pinfunction "VDD_6") (pintype "bidirectional"))
      (node (ref "U$55") (pin "6") (pinfunction "VDD_6") (pintype "bidirectional"))
      (node (ref "U$56") (pin "6") (pinfunction "VDD_6") (pintype "bidirectional"))
      (node (ref "U$57") (pin "6") (pinfunction "VDD_6") (pintype "bidirectional"))
      (node (ref "U$66") (pin "6") (pinfunction "VDD_6") (pintype "bidirectional"))
      (node (ref "U$68") (pin "6") (pinfunction "VDD_6") (pintype "bidirectional"))
      (node (ref "U$69") (pin "6") (pinfunction "VDD_6") (pintype "bidirectional"))
      (node (ref "U$70") (pin "6") (pinfunction "VDD_6") (pintype "bidirectional"))
      (node (ref "U$79") (pin "6") (pinfunction "VDD_6") (pintype "bidirectional"))
      (node (ref "U$81") (pin "6") (pinfunction "VDD_6") (pintype "bidirectional"))
      (node (ref "U$82") (pin "6") (pinfunction "VDD_6") (pintype "bidirectional"))
      (node (ref "U$83") (pin "6") (pinfunction "VDD_6") (pintype "bidirectional"))
      (node (ref "U$92") (pin "6") (pinfunction "VDD_6") (pintype "bidirectional"))
      (node (ref "U$94") (pin "6") (pinfunction "VDD_6") (pintype "bidirectional"))
      (node (ref "U$95") (pin "6") (pinfunction "VDD_6") (pintype "bidirectional"))
      (node (ref "U$96") (pin "6") (pinfunction "VDD_6") (pintype "bidirectional"))
    )
    (net (code "142") (name "unconnected-(U$2-Q'-Pad9)") (class "Default")
      (node (ref "U$2") (pin "9") (pinfunction "Q'_9") (pintype "bidirectional"))
    )
    (net (code "143") (name "unconnected-(U$15-Q'-Pad9)") (class "Default")
      (node (ref "U$15") (pin "9") (pinfunction "Q'_9") (pintype "bidirectional"))
    )
    (net (code "144") (name "unconnected-(U$28-Q'-Pad9)") (class "Default")
      (node (ref "U$28") (pin "9") (pinfunction "Q'_9") (pintype "bidirectional"))
    )
    (net (code "145") (name "unconnected-(U$41-Q'-Pad9)") (class "Default")
      (node (ref "U$41") (pin "9") (pinfunction "Q'_9") (pintype "bidirectional"))
    )
    (net (code "146") (name "unconnected-(U$54-Q'-Pad9)") (class "Default")
      (node (ref "U$54") (pin "9") (pinfunction "Q'_9") (pintype "bidirectional"))
    )
    (net (code "147") (name "unconnected-(U$67-Q'-Pad9)") (class "Default")
      (node (ref "U$67") (pin "9") (pinfunction "Q'_9") (pintype "bidirectional"))
    )
    (net (code "148") (name "unconnected-(U$80-Q'-Pad9)") (class "Default")
      (node (ref "U$80") (pin "9") (pinfunction "Q'_9") (pintype "bidirectional"))
    )
    (net (code "149") (name "unconnected-(U$93-Q'-Pad9)") (class "Default")
      (node (ref "U$93") (pin "9") (pinfunction "Q'_9") (pintype "bidirectional"))
    )
  )
)
